# ZynqCoreBoard2.net
KiCad netlist of a schematic drawn in Altium Designer
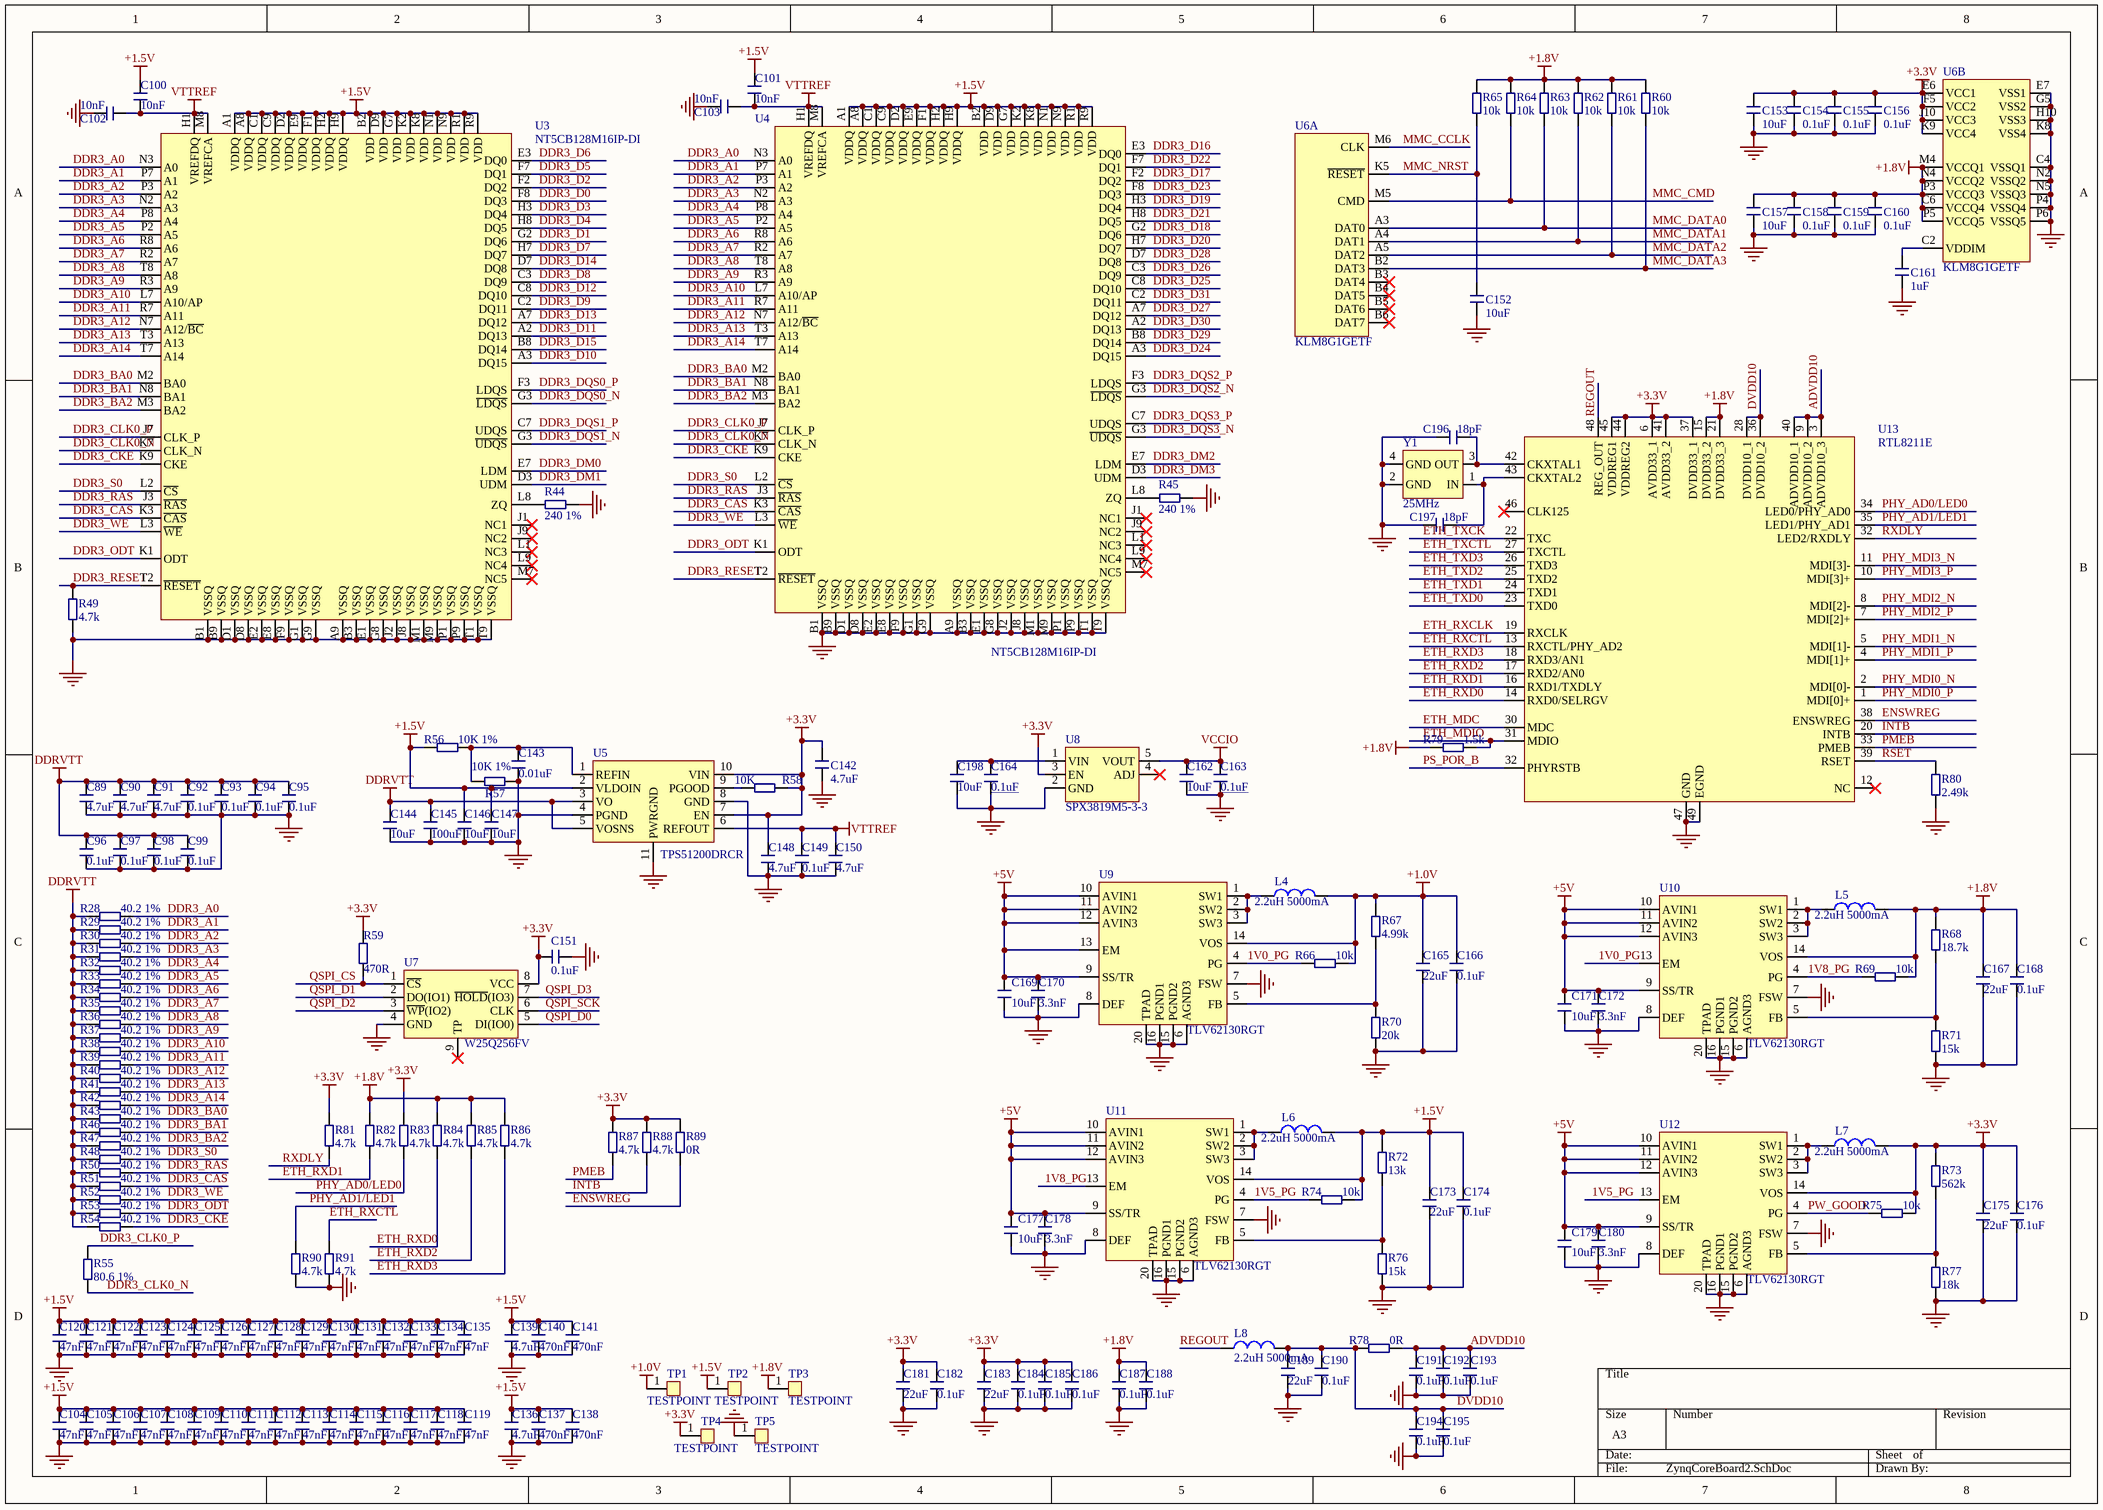
[diagram p0: ZynqCoreBoard2.SchDoc]

(export (version "E")
  (design (tool "Eeschema 10.0.6"))
  (components
    (comp (ref "C89")
      (value "4.7uF")
      (footprint "C0402")
      (libsource (lib "zynqCoreboard_SCHLIB") (part "C0402"))
    )
    (comp (ref "C90")
      (value "4.7uF")
      (footprint "C0402")
      (libsource (lib "zynqCoreboard_SCHLIB") (part "C0402"))
    )
    (comp (ref "C91")
      (value "4.7uF")
      (footprint "C0402")
      (libsource (lib "zynqCoreboard_SCHLIB") (part "C0402"))
    )
    (comp (ref "C92")
      (value "0.1uF")
      (footprint "C0402")
      (libsource (lib "zynqCoreboard_SCHLIB") (part "C0402"))
    )
    (comp (ref "C93")
      (value "0.1uF")
      (footprint "C0402")
      (libsource (lib "zynqCoreboard_SCHLIB") (part "C0402"))
    )
    (comp (ref "C94")
      (value "0.1uF")
      (footprint "C0402")
      (libsource (lib "zynqCoreboard_SCHLIB") (part "C0402"))
    )
    (comp (ref "C95")
      (value "0.1uF")
      (footprint "C0402")
      (libsource (lib "zynqCoreboard_SCHLIB") (part "C0402"))
    )
    (comp (ref "C96")
      (value "0.1uF")
      (footprint "C0402")
      (libsource (lib "zynqCoreboard_SCHLIB") (part "C0402"))
    )
    (comp (ref "C97")
      (value "0.1uF")
      (footprint "C0402")
      (libsource (lib "zynqCoreboard_SCHLIB") (part "C0402"))
    )
    (comp (ref "C98")
      (value "0.1uF")
      (footprint "C0402")
      (libsource (lib "zynqCoreboard_SCHLIB") (part "C0402"))
    )
    (comp (ref "C99")
      (value "0.1uF")
      (footprint "C0402")
      (libsource (lib "zynqCoreboard_SCHLIB") (part "C0402"))
    )
    (comp (ref "C100")
      (value "10nF")
      (footprint "C0402")
      (libsource (lib "zynqCoreboard_SCHLIB") (part "C0402"))
    )
    (comp (ref "C101")
      (value "10nF")
      (footprint "C0402")
      (libsource (lib "zynqCoreboard_SCHLIB") (part "C0402"))
    )
    (comp (ref "C102")
      (value "10nF")
      (footprint "C0402")
      (libsource (lib "zynqCoreboard_SCHLIB") (part "C0402"))
    )
    (comp (ref "C103")
      (value "10nF")
      (footprint "C0402")
      (libsource (lib "zynqCoreboard_SCHLIB") (part "C0402"))
    )
    (comp (ref "C104")
      (value "47nF")
      (footprint "C0402")
      (libsource (lib "zynqCoreboard_SCHLIB") (part "C0402"))
    )
    (comp (ref "C105")
      (value "47nF")
      (footprint "C0402")
      (libsource (lib "zynqCoreboard_SCHLIB") (part "C0402"))
    )
    (comp (ref "C106")
      (value "47nF")
      (footprint "C0402")
      (libsource (lib "zynqCoreboard_SCHLIB") (part "C0402"))
    )
    (comp (ref "C107")
      (value "47nF")
      (footprint "C0402")
      (libsource (lib "zynqCoreboard_SCHLIB") (part "C0402"))
    )
    (comp (ref "C108")
      (value "47nF")
      (footprint "C0402")
      (libsource (lib "zynqCoreboard_SCHLIB") (part "C0402"))
    )
    (comp (ref "C109")
      (value "47nF")
      (footprint "C0402")
      (libsource (lib "zynqCoreboard_SCHLIB") (part "C0402"))
    )
    (comp (ref "C110")
      (value "47nF")
      (footprint "C0402")
      (libsource (lib "zynqCoreboard_SCHLIB") (part "C0402"))
    )
    (comp (ref "C111")
      (value "47nF")
      (footprint "C0402")
      (libsource (lib "zynqCoreboard_SCHLIB") (part "C0402"))
    )
    (comp (ref "C112")
      (value "47nF")
      (footprint "C0402")
      (libsource (lib "zynqCoreboard_SCHLIB") (part "C0402"))
    )
    (comp (ref "C113")
      (value "47nF")
      (footprint "C0402")
      (libsource (lib "zynqCoreboard_SCHLIB") (part "C0402"))
    )
    (comp (ref "C114")
      (value "47nF")
      (footprint "C0402")
      (libsource (lib "zynqCoreboard_SCHLIB") (part "C0402"))
    )
    (comp (ref "C115")
      (value "47nF")
      (footprint "C0402")
      (libsource (lib "zynqCoreboard_SCHLIB") (part "C0402"))
    )
    (comp (ref "C116")
      (value "47nF")
      (footprint "C0402")
      (libsource (lib "zynqCoreboard_SCHLIB") (part "C0402"))
    )
    (comp (ref "C117")
      (value "47nF")
      (footprint "C0402")
      (libsource (lib "zynqCoreboard_SCHLIB") (part "C0402"))
    )
    (comp (ref "C118")
      (value "47nF")
      (footprint "C0402")
      (libsource (lib "zynqCoreboard_SCHLIB") (part "C0402"))
    )
    (comp (ref "C119")
      (value "47nF")
      (footprint "C0402")
      (libsource (lib "zynqCoreboard_SCHLIB") (part "C0402"))
    )
    (comp (ref "C120")
      (value "47nF")
      (footprint "C0402")
      (libsource (lib "zynqCoreboard_SCHLIB") (part "C0402"))
    )
    (comp (ref "C121")
      (value "47nF")
      (footprint "C0402")
      (libsource (lib "zynqCoreboard_SCHLIB") (part "C0402"))
    )
    (comp (ref "C122")
      (value "47nF")
      (footprint "C0402")
      (libsource (lib "zynqCoreboard_SCHLIB") (part "C0402"))
    )
    (comp (ref "C123")
      (value "47nF")
      (footprint "C0402")
      (libsource (lib "zynqCoreboard_SCHLIB") (part "C0402"))
    )
    (comp (ref "C124")
      (value "47nF")
      (footprint "C0402")
      (libsource (lib "zynqCoreboard_SCHLIB") (part "C0402"))
    )
    (comp (ref "C125")
      (value "47nF")
      (footprint "C0402")
      (libsource (lib "zynqCoreboard_SCHLIB") (part "C0402"))
    )
    (comp (ref "C126")
      (value "47nF")
      (footprint "C0402")
      (libsource (lib "zynqCoreboard_SCHLIB") (part "C0402"))
    )
    (comp (ref "C127")
      (value "47nF")
      (footprint "C0402")
      (libsource (lib "zynqCoreboard_SCHLIB") (part "C0402"))
    )
    (comp (ref "C128")
      (value "47nF")
      (footprint "C0402")
      (libsource (lib "zynqCoreboard_SCHLIB") (part "C0402"))
    )
    (comp (ref "C129")
      (value "47nF")
      (footprint "C0402")
      (libsource (lib "zynqCoreboard_SCHLIB") (part "C0402"))
    )
    (comp (ref "C130")
      (value "47nF")
      (footprint "C0402")
      (libsource (lib "zynqCoreboard_SCHLIB") (part "C0402"))
    )
    (comp (ref "C131")
      (value "47nF")
      (footprint "C0402")
      (libsource (lib "zynqCoreboard_SCHLIB") (part "C0402"))
    )
    (comp (ref "C132")
      (value "47nF")
      (footprint "C0402")
      (libsource (lib "zynqCoreboard_SCHLIB") (part "C0402"))
    )
    (comp (ref "C133")
      (value "47nF")
      (footprint "C0402")
      (libsource (lib "zynqCoreboard_SCHLIB") (part "C0402"))
    )
    (comp (ref "C134")
      (value "47nF")
      (footprint "C0402")
      (libsource (lib "zynqCoreboard_SCHLIB") (part "C0402"))
    )
    (comp (ref "C135")
      (value "47nF")
      (footprint "C0402")
      (libsource (lib "zynqCoreboard_SCHLIB") (part "C0402"))
    )
    (comp (ref "C136")
      (value "4.7uF")
      (footprint "C0402")
      (libsource (lib "zynqCoreboard_SCHLIB") (part "C0402"))
    )
    (comp (ref "C137")
      (value "470nF")
      (footprint "C0402")
      (libsource (lib "zynqCoreboard_SCHLIB") (part "C0402"))
    )
    (comp (ref "C138")
      (value "470nF")
      (footprint "C0402")
      (libsource (lib "zynqCoreboard_SCHLIB") (part "C0402"))
    )
    (comp (ref "C139")
      (value "4.7uF")
      (footprint "C0402")
      (libsource (lib "zynqCoreboard_SCHLIB") (part "C0402"))
    )
    (comp (ref "C140")
      (value "470nF")
      (footprint "C0402")
      (libsource (lib "zynqCoreboard_SCHLIB") (part "C0402"))
    )
    (comp (ref "C141")
      (value "470nF")
      (footprint "C0402")
      (libsource (lib "zynqCoreboard_SCHLIB") (part "C0402"))
    )
    (comp (ref "C142")
      (value "4.7uF")
      (footprint "C0402")
      (libsource (lib "zynqCoreboard_SCHLIB") (part "C0402"))
    )
    (comp (ref "C143")
      (value "0.01uF")
      (footprint "C0402")
      (libsource (lib "zynqCoreboard_SCHLIB") (part "C0402"))
    )
    (comp (ref "C144")
      (value "10uF")
      (footprint "C0603")
      (libsource (lib "zynqCoreboard_SCHLIB") (part "C0603"))
    )
    (comp (ref "C145")
      (value "100uF")
      (footprint "C1206")
      (libsource (lib "zynqCoreboard_SCHLIB") (part "C1206"))
    )
    (comp (ref "C146")
      (value "10uF")
      (footprint "C0603")
      (libsource (lib "zynqCoreboard_SCHLIB") (part "C0603"))
    )
    (comp (ref "C147")
      (value "10uF")
      (footprint "C0603")
      (libsource (lib "zynqCoreboard_SCHLIB") (part "C0603"))
    )
    (comp (ref "C148")
      (value "4.7uF")
      (footprint "C0402")
      (libsource (lib "zynqCoreboard_SCHLIB") (part "C0402"))
    )
    (comp (ref "C149")
      (value "0.1uF")
      (footprint "C0402")
      (libsource (lib "zynqCoreboard_SCHLIB") (part "C0402"))
    )
    (comp (ref "C150")
      (value "4.7uF")
      (footprint "C0402")
      (libsource (lib "zynqCoreboard_SCHLIB") (part "C0402"))
    )
    (comp (ref "C151")
      (value "0.1uF")
      (footprint "C0402")
      (libsource (lib "zynqCoreboard_SCHLIB") (part "C0402"))
    )
    (comp (ref "C152")
      (value "10uF")
      (footprint "C0603")
      (libsource (lib "zynqCoreboard_SCHLIB") (part "C0603"))
    )
    (comp (ref "C153")
      (value "10uF")
      (footprint "C0603")
      (libsource (lib "zynqCoreboard_SCHLIB") (part "C0603"))
    )
    (comp (ref "C154")
      (value "0.1uF")
      (footprint "C0402")
      (libsource (lib "zynqCoreboard_SCHLIB") (part "C0402"))
    )
    (comp (ref "C155")
      (value "0.1uF")
      (footprint "C0402")
      (libsource (lib "zynqCoreboard_SCHLIB") (part "C0402"))
    )
    (comp (ref "C156")
      (value "0.1uF")
      (footprint "C0402")
      (libsource (lib "zynqCoreboard_SCHLIB") (part "C0402"))
    )
    (comp (ref "C157")
      (value "10uF")
      (footprint "C0603")
      (libsource (lib "zynqCoreboard_SCHLIB") (part "C0603"))
    )
    (comp (ref "C158")
      (value "0.1uF")
      (footprint "C0402")
      (libsource (lib "zynqCoreboard_SCHLIB") (part "C0402"))
    )
    (comp (ref "C159")
      (value "0.1uF")
      (footprint "C0402")
      (libsource (lib "zynqCoreboard_SCHLIB") (part "C0402"))
    )
    (comp (ref "C160")
      (value "0.1uF")
      (footprint "C0402")
      (libsource (lib "zynqCoreboard_SCHLIB") (part "C0402"))
    )
    (comp (ref "C161")
      (value "1uF")
      (footprint "C0402")
      (libsource (lib "zynqCoreboard_SCHLIB") (part "C0402"))
    )
    (comp (ref "C162")
      (value "10uF")
      (footprint "C0805")
      (libsource (lib "zynqCoreboard_SCHLIB") (part "C0805"))
    )
    (comp (ref "C163")
      (value "0.1uF")
      (footprint "C0402")
      (libsource (lib "zynqCoreboard_SCHLIB") (part "C0402"))
    )
    (comp (ref "C164")
      (value "0.1uF")
      (footprint "C0402")
      (libsource (lib "zynqCoreboard_SCHLIB") (part "C0402"))
    )
    (comp (ref "C165")
      (value "22uF")
      (footprint "C0805")
      (libsource (lib "zynqCoreboard_SCHLIB") (part "C0805"))
    )
    (comp (ref "C166")
      (value "0.1uF")
      (footprint "C0402")
      (libsource (lib "zynqCoreboard_SCHLIB") (part "C0402"))
    )
    (comp (ref "C167")
      (value "22uF")
      (footprint "C0805")
      (libsource (lib "zynqCoreboard_SCHLIB") (part "C0805"))
    )
    (comp (ref "C168")
      (value "0.1uF")
      (footprint "C0402")
      (libsource (lib "zynqCoreboard_SCHLIB") (part "C0402"))
    )
    (comp (ref "C169")
      (value "10uF")
      (footprint "C0603")
      (libsource (lib "zynqCoreboard_SCHLIB") (part "C0603"))
    )
    (comp (ref "C170")
      (value "3.3nF")
      (footprint "C0402")
      (libsource (lib "zynqCoreboard_SCHLIB") (part "C0402"))
    )
    (comp (ref "C171")
      (value "10uF")
      (footprint "C0603")
      (libsource (lib "zynqCoreboard_SCHLIB") (part "C0603"))
    )
    (comp (ref "C172")
      (value "3.3nF")
      (footprint "C0402")
      (libsource (lib "zynqCoreboard_SCHLIB") (part "C0402"))
    )
    (comp (ref "C173")
      (value "22uF")
      (footprint "C0805")
      (libsource (lib "zynqCoreboard_SCHLIB") (part "C0805"))
    )
    (comp (ref "C174")
      (value "0.1uF")
      (footprint "C0402")
      (libsource (lib "zynqCoreboard_SCHLIB") (part "C0402"))
    )
    (comp (ref "C175")
      (value "22uF")
      (footprint "C0805")
      (libsource (lib "zynqCoreboard_SCHLIB") (part "C0805"))
    )
    (comp (ref "C176")
      (value "0.1uF")
      (footprint "C0402")
      (libsource (lib "zynqCoreboard_SCHLIB") (part "C0402"))
    )
    (comp (ref "C177")
      (value "10uF")
      (footprint "C0603")
      (libsource (lib "zynqCoreboard_SCHLIB") (part "C0603"))
    )
    (comp (ref "C178")
      (value "3.3nF")
      (footprint "C0402")
      (libsource (lib "zynqCoreboard_SCHLIB") (part "C0402"))
    )
    (comp (ref "C179")
      (value "10uF")
      (footprint "C0603")
      (libsource (lib "zynqCoreboard_SCHLIB") (part "C0603"))
    )
    (comp (ref "C180")
      (value "3.3nF")
      (footprint "C0402")
      (libsource (lib "zynqCoreboard_SCHLIB") (part "C0402"))
    )
    (comp (ref "C181")
      (value "22uF")
      (footprint "C0805")
      (libsource (lib "zynqCoreboard_SCHLIB") (part "C0805"))
    )
    (comp (ref "C182")
      (value "0.1uF")
      (footprint "C0402")
      (libsource (lib "zynqCoreboard_SCHLIB") (part "C0402"))
    )
    (comp (ref "C183")
      (value "22uF")
      (footprint "C0805")
      (libsource (lib "zynqCoreboard_SCHLIB") (part "C0805"))
    )
    (comp (ref "C184")
      (value "0.1uF")
      (footprint "C0402")
      (libsource (lib "zynqCoreboard_SCHLIB") (part "C0402"))
    )
    (comp (ref "C185")
      (value "0.1uF")
      (footprint "C0402")
      (libsource (lib "zynqCoreboard_SCHLIB") (part "C0402"))
    )
    (comp (ref "C186")
      (value "0.1uF")
      (footprint "C0402")
      (libsource (lib "zynqCoreboard_SCHLIB") (part "C0402"))
    )
    (comp (ref "C187")
      (value "0.1uF")
      (footprint "C0402")
      (libsource (lib "zynqCoreboard_SCHLIB") (part "C0402"))
    )
    (comp (ref "C188")
      (value "0.1uF")
      (footprint "C0402")
      (libsource (lib "zynqCoreboard_SCHLIB") (part "C0402"))
    )
    (comp (ref "C189")
      (value "22uF")
      (footprint "C0603")
      (libsource (lib "zynqCoreboard_SCHLIB") (part "C0603"))
    )
    (comp (ref "C190")
      (value "0.1uF")
      (footprint "C0402")
      (libsource (lib "zynqCoreboard_SCHLIB") (part "C0402"))
    )
    (comp (ref "C191")
      (value "0.1uF")
      (footprint "C0402")
      (libsource (lib "zynqCoreboard_SCHLIB") (part "C0402"))
    )
    (comp (ref "C192")
      (value "0.1uF")
      (footprint "C0402")
      (libsource (lib "zynqCoreboard_SCHLIB") (part "C0402"))
    )
    (comp (ref "C193")
      (value "0.1uF")
      (footprint "C0402")
      (libsource (lib "zynqCoreboard_SCHLIB") (part "C0402"))
    )
    (comp (ref "C194")
      (value "0.1uF")
      (footprint "C0402")
      (libsource (lib "zynqCoreboard_SCHLIB") (part "C0402"))
    )
    (comp (ref "C195")
      (value "0.1uF")
      (footprint "C0402")
      (libsource (lib "zynqCoreboard_SCHLIB") (part "C0402"))
    )
    (comp (ref "C196")
      (value "18pF")
      (footprint "C0402")
      (libsource (lib "zynqCoreboard_SCHLIB") (part "C0402"))
    )
    (comp (ref "C197")
      (value "18pF")
      (footprint "C0402")
      (libsource (lib "zynqCoreboard_SCHLIB") (part "C0402"))
    )
    (comp (ref "C198")
      (value "10uF")
      (footprint "C0805")
      (libsource (lib "zynqCoreboard_SCHLIB") (part "C0805"))
    )
    (comp (ref "L4")
      (value "2.2uH 5000mA")
      (footprint "L-SMD-0630")
      (libsource (lib "zynqCoreboard_SCHLIB") (part "L_2.2uH_5000mA"))
    )
    (comp (ref "L5")
      (value "2.2uH 5000mA")
      (footprint "L-SMD-0630")
      (libsource (lib "zynqCoreboard_SCHLIB") (part "L_2.2uH_5000mA"))
    )
    (comp (ref "L6")
      (value "2.2uH 5000mA")
      (footprint "L-SMD-0630")
      (libsource (lib "zynqCoreboard_SCHLIB") (part "L_2.2uH_5000mA"))
    )
    (comp (ref "L7")
      (value "2.2uH 5000mA")
      (footprint "L-SMD-0630")
      (libsource (lib "zynqCoreboard_SCHLIB") (part "L_2.2uH_5000mA"))
    )
    (comp (ref "L8")
      (value "2.2uH 5000mA")
      (footprint "L0603")
      (libsource (lib "zynqCoreboard_SCHLIB") (part "L0603"))
    )
    (comp (ref "R28")
      (value "40.2 1%")
      (footprint "R0402")
      (libsource (lib "zynqCoreboard_SCHLIB") (part "R0402"))
    )
    (comp (ref "R29")
      (value "40.2 1%")
      (footprint "R0402")
      (libsource (lib "zynqCoreboard_SCHLIB") (part "R0402"))
    )
    (comp (ref "R30")
      (value "40.2 1%")
      (footprint "R0402")
      (libsource (lib "zynqCoreboard_SCHLIB") (part "R0402"))
    )
    (comp (ref "R31")
      (value "40.2 1%")
      (footprint "R0402")
      (libsource (lib "zynqCoreboard_SCHLIB") (part "R0402"))
    )
    (comp (ref "R32")
      (value "40.2 1%")
      (footprint "R0402")
      (libsource (lib "zynqCoreboard_SCHLIB") (part "R0402"))
    )
    (comp (ref "R33")
      (value "40.2 1%")
      (footprint "R0402")
      (libsource (lib "zynqCoreboard_SCHLIB") (part "R0402"))
    )
    (comp (ref "R34")
      (value "40.2 1%")
      (footprint "R0402")
      (libsource (lib "zynqCoreboard_SCHLIB") (part "R0402"))
    )
    (comp (ref "R35")
      (value "40.2 1%")
      (footprint "R0402")
      (libsource (lib "zynqCoreboard_SCHLIB") (part "R0402"))
    )
    (comp (ref "R36")
      (value "40.2 1%")
      (footprint "R0402")
      (libsource (lib "zynqCoreboard_SCHLIB") (part "R0402"))
    )
    (comp (ref "R37")
      (value "40.2 1%")
      (footprint "R0402")
      (libsource (lib "zynqCoreboard_SCHLIB") (part "R0402"))
    )
    (comp (ref "R38")
      (value "40.2 1%")
      (footprint "R0402")
      (libsource (lib "zynqCoreboard_SCHLIB") (part "R0402"))
    )
    (comp (ref "R39")
      (value "40.2 1%")
      (footprint "R0402")
      (libsource (lib "zynqCoreboard_SCHLIB") (part "R0402"))
    )
    (comp (ref "R40")
      (value "40.2 1%")
      (footprint "R0402")
      (libsource (lib "zynqCoreboard_SCHLIB") (part "R0402"))
    )
    (comp (ref "R41")
      (value "40.2 1%")
      (footprint "R0402")
      (libsource (lib "zynqCoreboard_SCHLIB") (part "R0402"))
    )
    (comp (ref "R42")
      (value "40.2 1%")
      (footprint "R0402")
      (libsource (lib "zynqCoreboard_SCHLIB") (part "R0402"))
    )
    (comp (ref "R43")
      (value "40.2 1%")
      (footprint "R0402")
      (libsource (lib "zynqCoreboard_SCHLIB") (part "R0402"))
    )
    (comp (ref "R44")
      (value "240 1%")
      (footprint "R0402")
      (libsource (lib "zynqCoreboard_SCHLIB") (part "R0402"))
    )
    (comp (ref "R45")
      (value "240 1%")
      (footprint "R0402")
      (libsource (lib "zynqCoreboard_SCHLIB") (part "R0402"))
    )
    (comp (ref "R46")
      (value "40.2 1%")
      (footprint "R0402")
      (libsource (lib "zynqCoreboard_SCHLIB") (part "R0402"))
    )
    (comp (ref "R47")
      (value "40.2 1%")
      (footprint "R0402")
      (libsource (lib "zynqCoreboard_SCHLIB") (part "R0402"))
    )
    (comp (ref "R48")
      (value "40.2 1%")
      (footprint "R0402")
      (libsource (lib "zynqCoreboard_SCHLIB") (part "R0402"))
    )
    (comp (ref "R49")
      (value "4.7k")
      (footprint "R0402")
      (libsource (lib "zynqCoreboard_SCHLIB") (part "R0402"))
    )
    (comp (ref "R50")
      (value "40.2 1%")
      (footprint "R0402")
      (libsource (lib "zynqCoreboard_SCHLIB") (part "R0402"))
    )
    (comp (ref "R51")
      (value "40.2 1%")
      (footprint "R0402")
      (libsource (lib "zynqCoreboard_SCHLIB") (part "R0402"))
    )
    (comp (ref "R52")
      (value "40.2 1%")
      (footprint "R0402")
      (libsource (lib "zynqCoreboard_SCHLIB") (part "R0402"))
    )
    (comp (ref "R53")
      (value "40.2 1%")
      (footprint "R0402")
      (libsource (lib "zynqCoreboard_SCHLIB") (part "R0402"))
    )
    (comp (ref "R54")
      (value "40.2 1%")
      (footprint "R0402")
      (libsource (lib "zynqCoreboard_SCHLIB") (part "R0402"))
    )
    (comp (ref "R55")
      (value "80.6 1%")
      (footprint "R0402")
      (libsource (lib "zynqCoreboard_SCHLIB") (part "R0402"))
    )
    (comp (ref "R56")
      (value "10K 1%")
      (footprint "R0402")
      (libsource (lib "zynqCoreboard_SCHLIB") (part "R0402"))
    )
    (comp (ref "R57")
      (value "10K 1%")
      (footprint "R0402")
      (libsource (lib "zynqCoreboard_SCHLIB") (part "R0402"))
    )
    (comp (ref "R58")
      (value "10K")
      (footprint "R0402")
      (libsource (lib "zynqCoreboard_SCHLIB") (part "R0402"))
    )
    (comp (ref "R59")
      (value "470R")
      (footprint "R0402")
      (libsource (lib "zynqCoreboard_SCHLIB") (part "R0402"))
    )
    (comp (ref "R60")
      (value "10k")
      (footprint "R0402")
      (libsource (lib "zynqCoreboard_SCHLIB") (part "R0402"))
    )
    (comp (ref "R61")
      (value "10k")
      (footprint "R0402")
      (libsource (lib "zynqCoreboard_SCHLIB") (part "R0402"))
    )
    (comp (ref "R62")
      (value "10k")
      (footprint "R0402")
      (libsource (lib "zynqCoreboard_SCHLIB") (part "R0402"))
    )
    (comp (ref "R63")
      (value "10k")
      (footprint "R0402")
      (libsource (lib "zynqCoreboard_SCHLIB") (part "R0402"))
    )
    (comp (ref "R64")
      (value "10k")
      (footprint "R0402")
      (libsource (lib "zynqCoreboard_SCHLIB") (part "R0402"))
    )
    (comp (ref "R65")
      (value "10k")
      (footprint "R0402")
      (libsource (lib "zynqCoreboard_SCHLIB") (part "R0402"))
    )
    (comp (ref "R66")
      (value "10k")
      (footprint "R0402")
      (libsource (lib "zynqCoreboard_SCHLIB") (part "R0402"))
    )
    (comp (ref "R67")
      (value "4.99k")
      (footprint "R0402")
      (libsource (lib "zynqCoreboard_SCHLIB") (part "R0402"))
    )
    (comp (ref "R68")
      (value "18.7k")
      (footprint "R0402")
      (libsource (lib "zynqCoreboard_SCHLIB") (part "R0402"))
    )
    (comp (ref "R69")
      (value "10k")
      (footprint "R0402")
      (libsource (lib "zynqCoreboard_SCHLIB") (part "R0402"))
    )
    (comp (ref "R70")
      (value "20k")
      (footprint "R0402")
      (libsource (lib "zynqCoreboard_SCHLIB") (part "R0402"))
    )
    (comp (ref "R71")
      (value "15k")
      (footprint "R0402")
      (libsource (lib "zynqCoreboard_SCHLIB") (part "R0402"))
    )
    (comp (ref "R72")
      (value "13k")
      (footprint "R0402")
      (libsource (lib "zynqCoreboard_SCHLIB") (part "R0402"))
    )
    (comp (ref "R73")
      (value "562k")
      (footprint "R0402")
      (libsource (lib "zynqCoreboard_SCHLIB") (part "R0402"))
    )
    (comp (ref "R74")
      (value "10k")
      (footprint "R0402")
      (libsource (lib "zynqCoreboard_SCHLIB") (part "R0402"))
    )
    (comp (ref "R75")
      (value "10k")
      (footprint "R0402")
      (libsource (lib "zynqCoreboard_SCHLIB") (part "R0402"))
    )
    (comp (ref "R76")
      (value "15k")
      (footprint "R0402")
      (libsource (lib "zynqCoreboard_SCHLIB") (part "R0402"))
    )
    (comp (ref "R77")
      (value "18k")
      (footprint "R0402")
      (libsource (lib "zynqCoreboard_SCHLIB") (part "R0402"))
    )
    (comp (ref "R78")
      (value "0R")
      (footprint "R0402")
      (libsource (lib "zynqCoreboard_SCHLIB") (part "R0402"))
    )
    (comp (ref "R79")
      (value "1.5k")
      (footprint "R0402")
      (libsource (lib "zynqCoreboard_SCHLIB") (part "R0402"))
    )
    (comp (ref "R80")
      (value "2.49k")
      (footprint "R0402")
      (libsource (lib "zynqCoreboard_SCHLIB") (part "R0402"))
    )
    (comp (ref "R81")
      (value "4.7k")
      (footprint "R0402")
      (libsource (lib "zynqCoreboard_SCHLIB") (part "R0402"))
    )
    (comp (ref "R82")
      (value "4.7k")
      (footprint "R0402")
      (libsource (lib "zynqCoreboard_SCHLIB") (part "R0402"))
    )
    (comp (ref "R83")
      (value "4.7k")
      (footprint "R0402")
      (libsource (lib "zynqCoreboard_SCHLIB") (part "R0402"))
    )
    (comp (ref "R84")
      (value "4.7k")
      (footprint "R0402")
      (libsource (lib "zynqCoreboard_SCHLIB") (part "R0402"))
    )
    (comp (ref "R85")
      (value "4.7k")
      (footprint "R0402")
      (libsource (lib "zynqCoreboard_SCHLIB") (part "R0402"))
    )
    (comp (ref "R86")
      (value "4.7k")
      (footprint "R0402")
      (libsource (lib "zynqCoreboard_SCHLIB") (part "R0402"))
    )
    (comp (ref "R87")
      (value "4.7k")
      (footprint "R0402")
      (libsource (lib "zynqCoreboard_SCHLIB") (part "R0402"))
    )
    (comp (ref "R88")
      (value "4.7k")
      (footprint "R0402")
      (libsource (lib "zynqCoreboard_SCHLIB") (part "R0402"))
    )
    (comp (ref "R89")
      (value "0R")
      (footprint "R0402")
      (libsource (lib "zynqCoreboard_SCHLIB") (part "R0402"))
    )
    (comp (ref "R90")
      (value "4.7k")
      (footprint "R0402")
      (libsource (lib "zynqCoreboard_SCHLIB") (part "R0402"))
    )
    (comp (ref "R91")
      (value "4.7k")
      (footprint "R0402")
      (libsource (lib "zynqCoreboard_SCHLIB") (part "R0402"))
    )
    (comp (ref "TP1")
      (value "TESTPOINT")
      (footprint "FPAD_1")
      (libsource (lib "zynqCoreboard_SCHLIB") (part "TESTPOINT"))
    )
    (comp (ref "TP2")
      (value "TESTPOINT")
      (footprint "FPAD_1")
      (libsource (lib "zynqCoreboard_SCHLIB") (part "TESTPOINT"))
    )
    (comp (ref "TP3")
      (value "TESTPOINT")
      (footprint "FPAD_1")
      (libsource (lib "zynqCoreboard_SCHLIB") (part "TESTPOINT"))
    )
    (comp (ref "TP4")
      (value "TESTPOINT")
      (footprint "FPAD_1")
      (libsource (lib "zynqCoreboard_SCHLIB") (part "TESTPOINT"))
    )
    (comp (ref "TP5")
      (value "TESTPOINT")
      (footprint "FPAD_1")
      (libsource (lib "zynqCoreboard_SCHLIB") (part "TESTPOINT"))
    )
    (comp (ref "U3")
      (value "NT5CB128M16IP-DI")
      (footprint "FBGA_96")
      (libsource (lib "zynqCoreboard_SCHLIB") (part "NT5CB128M16IP-DI"))
    )
    (comp (ref "U4")
      (value "NT5CB128M16IP-DI")
      (footprint "FBGA_96")
      (libsource (lib "zynqCoreboard_SCHLIB") (part "NT5CB128M16IP-DI"))
    )
    (comp (ref "U5")
      (value "TPS51200DRCR")
      (footprint "TPS_QFN10")
      (libsource (lib "zynqCoreboard_SCHLIB") (part "TPS51200DRCR"))
    )
    (comp (ref "U6")
      (value "KLM8G1GETF")
      (footprint "VFBGA")
      (libsource (lib "zynqCoreboard_SCHLIB") (part "KLM8G1GETF"))
    )
    (comp (ref "U7")
      (value "W25Q256FV")
      (footprint "W25Q256FV")
      (libsource (lib "zynqCoreboard_SCHLIB") (part "W25Q256FV"))
    )
    (comp (ref "U8")
      (value "SPX3819M5-3-3")
      (footprint "SOT23-5")
      (libsource (lib "zynqCoreboard_SCHLIB") (part "SPX3819M5-3-3"))
    )
    (comp (ref "U9")
      (value "TLV62130RGT")
      (footprint "QFN16_3x3")
      (libsource (lib "zynqCoreboard_SCHLIB") (part "TLV62130RGT"))
    )
    (comp (ref "U10")
      (value "TLV62130RGT")
      (footprint "QFN16_3x3")
      (libsource (lib "zynqCoreboard_SCHLIB") (part "TLV62130RGT"))
    )
    (comp (ref "U11")
      (value "TLV62130RGT")
      (footprint "QFN16_3x3")
      (libsource (lib "zynqCoreboard_SCHLIB") (part "TLV62130RGT"))
    )
    (comp (ref "U12")
      (value "TLV62130RGT")
      (footprint "QFN16_3x3")
      (libsource (lib "zynqCoreboard_SCHLIB") (part "TLV62130RGT"))
    )
    (comp (ref "U13")
      (value "RTL8211E")
      (footprint "QFN48")
      (libsource (lib "zynqCoreboard_SCHLIB") (part "RTL8211E"))
    )
    (comp (ref "Y1")
      (value "25MHz")
      (footprint "OSC 3225-4P")
      (libsource (lib "zynqCoreboard_SCHLIB") (part "XTAL_25MHz_3225"))
    )
  )
  (nets
    (net (code "1") (name "+1.0V") (class "Default")
      (node (ref "C165") (pin "2") (pinfunction "2_2") (pintype "passive"))
      (node (ref "C166") (pin "2") (pinfunction "2_2") (pintype "passive"))
      (node (ref "L4") (pin "2") (pinfunction "2_2") (pintype "passive"))
      (node (ref "R66") (pin "2") (pinfunction "2_2") (pintype "passive"))
      (node (ref "R67") (pin "2") (pinfunction "2_2") (pintype "passive"))
      (node (ref "TP1") (pin "1") (pinfunction "1_1") (pintype "passive"))
      (node (ref "U9") (pin "14") (pinfunction "VOS_14") (pintype "passive"))
    )
    (net (code "2") (name "+1.5V") (class "Default")
      (node (ref "C100") (pin "2") (pinfunction "2_2") (pintype "passive"))
      (node (ref "C101") (pin "2") (pinfunction "2_2") (pintype "passive"))
      (node (ref "C104") (pin "2") (pinfunction "2_2") (pintype "passive"))
      (node (ref "C105") (pin "2") (pinfunction "2_2") (pintype "passive"))
      (node (ref "C106") (pin "2") (pinfunction "2_2") (pintype "passive"))
      (node (ref "C107") (pin "2") (pinfunction "2_2") (pintype "passive"))
      (node (ref "C108") (pin "2") (pinfunction "2_2") (pintype "passive"))
      (node (ref "C109") (pin "2") (pinfunction "2_2") (pintype "passive"))
      (node (ref "C110") (pin "2") (pinfunction "2_2") (pintype "passive"))
      (node (ref "C111") (pin "2") (pinfunction "2_2") (pintype "passive"))
      (node (ref "C112") (pin "2") (pinfunction "2_2") (pintype "passive"))
      (node (ref "C113") (pin "2") (pinfunction "2_2") (pintype "passive"))
      (node (ref "C114") (pin "2") (pinfunction "2_2") (pintype "passive"))
      (node (ref "C115") (pin "2") (pinfunction "2_2") (pintype "passive"))
      (node (ref "C116") (pin "2") (pinfunction "2_2") (pintype "passive"))
      (node (ref "C117") (pin "2") (pinfunction "2_2") (pintype "passive"))
      (node (ref "C118") (pin "2") (pinfunction "2_2") (pintype "passive"))
      (node (ref "C119") (pin "2") (pinfunction "2_2") (pintype "passive"))
      (node (ref "C120") (pin "2") (pinfunction "2_2") (pintype "passive"))
      (node (ref "C121") (pin "2") (pinfunction "2_2") (pintype "passive"))
      (node (ref "C122") (pin "2") (pinfunction "2_2") (pintype "passive"))
      (node (ref "C123") (pin "2") (pinfunction "2_2") (pintype "passive"))
      (node (ref "C124") (pin "2") (pinfunction "2_2") (pintype "passive"))
      (node (ref "C125") (pin "2") (pinfunction "2_2") (pintype "passive"))
      (node (ref "C126") (pin "2") (pinfunction "2_2") (pintype "passive"))
      (node (ref "C127") (pin "2") (pinfunction "2_2") (pintype "passive"))
      (node (ref "C128") (pin "2") (pinfunction "2_2") (pintype "passive"))
      (node (ref "C129") (pin "2") (pinfunction "2_2") (pintype "passive"))
      (node (ref "C130") (pin "2") (pinfunction "2_2") (pintype "passive"))
      (node (ref "C131") (pin "2") (pinfunction "2_2") (pintype "passive"))
      (node (ref "C132") (pin "2") (pinfunction "2_2") (pintype "passive"))
      (node (ref "C133") (pin "2") (pinfunction "2_2") (pintype "passive"))
      (node (ref "C134") (pin "2") (pinfunction "2_2") (pintype "passive"))
      (node (ref "C135") (pin "2") (pinfunction "2_2") (pintype "passive"))
      (node (ref "C136") (pin "2") (pinfunction "2_2") (pintype "passive"))
      (node (ref "C137") (pin "2") (pinfunction "2_2") (pintype "passive"))
      (node (ref "C138") (pin "2") (pinfunction "2_2") (pintype "passive"))
      (node (ref "C139") (pin "2") (pinfunction "2_2") (pintype "passive"))
      (node (ref "C140") (pin "2") (pinfunction "2_2") (pintype "passive"))
      (node (ref "C141") (pin "2") (pinfunction "2_2") (pintype "passive"))
      (node (ref "C146") (pin "2") (pinfunction "2_2") (pintype "passive"))
      (node (ref "C147") (pin "2") (pinfunction "2_2") (pintype "passive"))
      (node (ref "C173") (pin "2") (pinfunction "2_2") (pintype "passive"))
      (node (ref "C174") (pin "2") (pinfunction "2_2") (pintype "passive"))
      (node (ref "L6") (pin "2") (pinfunction "2_2") (pintype "passive"))
      (node (ref "R56") (pin "1") (pinfunction "1_1") (pintype "passive"))
      (node (ref "R72") (pin "2") (pinfunction "2_2") (pintype "passive"))
      (node (ref "R74") (pin "2") (pinfunction "2_2") (pintype "passive"))
      (node (ref "TP2") (pin "1") (pinfunction "1_1") (pintype "passive"))
      (node (ref "U11") (pin "14") (pinfunction "VOS_14") (pintype "passive"))
      (node (ref "U3") (pin "A1") (pinfunction "VDDQ_A1") (pintype "passive"))
      (node (ref "U3") (pin "A8") (pinfunction "VDDQ_A8") (pintype "passive"))
      (node (ref "U3") (pin "B2") (pinfunction "VDD_B2") (pintype "passive"))
      (node (ref "U3") (pin "C1") (pinfunction "VDDQ_C1") (pintype "passive"))
      (node (ref "U3") (pin "C9") (pinfunction "VDDQ_C9") (pintype "passive"))
      (node (ref "U3") (pin "D2") (pinfunction "VDDQ_D2") (pintype "passive"))
      (node (ref "U3") (pin "D9") (pinfunction "VDD_D9") (pintype "passive"))
      (node (ref "U3") (pin "E9") (pinfunction "VDDQ_E9") (pintype "passive"))
      (node (ref "U3") (pin "F1") (pinfunction "VDDQ_F1") (pintype "passive"))
      (node (ref "U3") (pin "G7") (pinfunction "VDD_G7") (pintype "passive"))
      (node (ref "U3") (pin "H2") (pinfunction "VDDQ_H2") (pintype "passive"))
      (node (ref "U3") (pin "H9") (pinfunction "VDDQ_H9") (pintype "passive"))
      (node (ref "U3") (pin "K2") (pinfunction "VDD_K2") (pintype "passive"))
      (node (ref "U3") (pin "K8") (pinfunction "VDD_K8") (pintype "passive"))
      (node (ref "U3") (pin "N1") (pinfunction "VDD_N1") (pintype "passive"))
      (node (ref "U3") (pin "N9") (pinfunction "VDD_N9") (pintype "passive"))
      (node (ref "U3") (pin "R1") (pinfunction "VDD_R1") (pintype "passive"))
      (node (ref "U3") (pin "R9") (pinfunction "VDD_R9") (pintype "passive"))
      (node (ref "U4") (pin "A1") (pinfunction "VDDQ_A1") (pintype "passive"))
      (node (ref "U4") (pin "A8") (pinfunction "VDDQ_A8") (pintype "passive"))
      (node (ref "U4") (pin "B2") (pinfunction "VDD_B2") (pintype "passive"))
      (node (ref "U4") (pin "C1") (pinfunction "VDDQ_C1") (pintype "passive"))
      (node (ref "U4") (pin "C9") (pinfunction "VDDQ_C9") (pintype "passive"))
      (node (ref "U4") (pin "D2") (pinfunction "VDDQ_D2") (pintype "passive"))
      (node (ref "U4") (pin "D9") (pinfunction "VDD_D9") (pintype "passive"))
      (node (ref "U4") (pin "E9") (pinfunction "VDDQ_E9") (pintype "passive"))
      (node (ref "U4") (pin "F1") (pinfunction "VDDQ_F1") (pintype "passive"))
      (node (ref "U4") (pin "G7") (pinfunction "VDD_G7") (pintype "passive"))
      (node (ref "U4") (pin "H2") (pinfunction "VDDQ_H2") (pintype "passive"))
      (node (ref "U4") (pin "H9") (pinfunction "VDDQ_H9") (pintype "passive"))
      (node (ref "U4") (pin "K2") (pinfunction "VDD_K2") (pintype "passive"))
      (node (ref "U4") (pin "K8") (pinfunction "VDD_K8") (pintype "passive"))
      (node (ref "U4") (pin "N1") (pinfunction "VDD_N1") (pintype "passive"))
      (node (ref "U4") (pin "N9") (pinfunction "VDD_N9") (pintype "passive"))
      (node (ref "U4") (pin "R1") (pinfunction "VDD_R1") (pintype "passive"))
      (node (ref "U4") (pin "R9") (pinfunction "VDD_R9") (pintype "passive"))
      (node (ref "U5") (pin "2") (pinfunction "VLDOIN_2") (pintype "passive"))
    )
    (net (code "3") (name "+1.8V") (class "Default")
      (node (ref "C157") (pin "2") (pinfunction "2_2") (pintype "passive"))
      (node (ref "C158") (pin "2") (pinfunction "2_2") (pintype "passive"))
      (node (ref "C159") (pin "2") (pinfunction "2_2") (pintype "passive"))
      (node (ref "C160") (pin "2") (pinfunction "2_2") (pintype "passive"))
      (node (ref "C167") (pin "2") (pinfunction "2_2") (pintype "passive"))
      (node (ref "C168") (pin "2") (pinfunction "2_2") (pintype "passive"))
      (node (ref "C187") (pin "2") (pinfunction "2_2") (pintype "passive"))
      (node (ref "C188") (pin "2") (pinfunction "2_2") (pintype "passive"))
      (node (ref "L5") (pin "2") (pinfunction "2_2") (pintype "passive"))
      (node (ref "R60") (pin "2") (pinfunction "2_2") (pintype "passive"))
      (node (ref "R61") (pin "2") (pinfunction "2_2") (pintype "passive"))
      (node (ref "R62") (pin "2") (pinfunction "2_2") (pintype "passive"))
      (node (ref "R63") (pin "2") (pinfunction "2_2") (pintype "passive"))
      (node (ref "R64") (pin "2") (pinfunction "2_2") (pintype "passive"))
      (node (ref "R65") (pin "2") (pinfunction "2_2") (pintype "passive"))
      (node (ref "R68") (pin "2") (pinfunction "2_2") (pintype "passive"))
      (node (ref "R69") (pin "2") (pinfunction "2_2") (pintype "passive"))
      (node (ref "R79") (pin "1") (pinfunction "1_1") (pintype "passive"))
      (node (ref "R82") (pin "2") (pinfunction "2_2") (pintype "passive"))
      (node (ref "R84") (pin "2") (pinfunction "2_2") (pintype "passive"))
      (node (ref "R85") (pin "2") (pinfunction "2_2") (pintype "passive"))
      (node (ref "R86") (pin "2") (pinfunction "2_2") (pintype "passive"))
      (node (ref "TP3") (pin "1") (pinfunction "1_1") (pintype "passive"))
      (node (ref "U10") (pin "14") (pinfunction "VOS_14") (pintype "passive"))
      (node (ref "U13") (pin "15") (pinfunction "DVDD33_2_15") (pintype "passive"))
      (node (ref "U13") (pin "21") (pinfunction "DVDD33_3_21") (pintype "passive"))
      (node (ref "U6") (pin "C6") (pinfunction "VCCQ4_C6") (pintype "passive"))
      (node (ref "U6") (pin "M4") (pinfunction "VCCQ1_M4") (pintype "passive"))
      (node (ref "U6") (pin "N4") (pinfunction "VCCQ2_N4") (pintype "passive"))
      (node (ref "U6") (pin "P3") (pinfunction "VCCQ3_P3") (pintype "passive"))
      (node (ref "U6") (pin "P5") (pinfunction "VCCQ5_P5") (pintype "passive"))
    )
    (net (code "4") (name "+3.3V") (class "Default")
      (node (ref "C142") (pin "2") (pinfunction "2_2") (pintype "passive"))
      (node (ref "C148") (pin "2") (pinfunction "2_2") (pintype "passive"))
      (node (ref "C151") (pin "2") (pinfunction "2_2") (pintype "passive"))
      (node (ref "C153") (pin "2") (pinfunction "2_2") (pintype "passive"))
      (node (ref "C154") (pin "2") (pinfunction "2_2") (pintype "passive"))
      (node (ref "C155") (pin "2") (pinfunction "2_2") (pintype "passive"))
      (node (ref "C156") (pin "2") (pinfunction "2_2") (pintype "passive"))
      (node (ref "C175") (pin "2") (pinfunction "2_2") (pintype "passive"))
      (node (ref "C176") (pin "2") (pinfunction "2_2") (pintype "passive"))
      (node (ref "C181") (pin "2") (pinfunction "2_2") (pintype "passive"))
      (node (ref "C182") (pin "2") (pinfunction "2_2") (pintype "passive"))
      (node (ref "C183") (pin "2") (pinfunction "2_2") (pintype "passive"))
      (node (ref "C184") (pin "2") (pinfunction "2_2") (pintype "passive"))
      (node (ref "C185") (pin "2") (pinfunction "2_2") (pintype "passive"))
      (node (ref "C186") (pin "2") (pinfunction "2_2") (pintype "passive"))
      (node (ref "L7") (pin "2") (pinfunction "2_2") (pintype "passive"))
      (node (ref "R58") (pin "2") (pinfunction "2_2") (pintype "passive"))
      (node (ref "R59") (pin "2") (pinfunction "2_2") (pintype "passive"))
      (node (ref "R73") (pin "2") (pinfunction "2_2") (pintype "passive"))
      (node (ref "R75") (pin "2") (pinfunction "2_2") (pintype "passive"))
      (node (ref "R81") (pin "2") (pinfunction "2_2") (pintype "passive"))
      (node (ref "R83") (pin "2") (pinfunction "2_2") (pintype "passive"))
      (node (ref "R87") (pin "2") (pinfunction "2_2") (pintype "passive"))
      (node (ref "R88") (pin "2") (pinfunction "2_2") (pintype "passive"))
      (node (ref "R89") (pin "2") (pinfunction "2_2") (pintype "passive"))
      (node (ref "TP4") (pin "1") (pinfunction "1_1") (pintype "passive"))
      (node (ref "U12") (pin "14") (pinfunction "VOS_14") (pintype "passive"))
      (node (ref "U13") (pin "37") (pinfunction "DVDD33_1_37") (pintype "passive"))
      (node (ref "U13") (pin "41") (pinfunction "AVDD33_2_41") (pintype "passive"))
      (node (ref "U13") (pin "44") (pinfunction "VDDREG2_44") (pintype "passive"))
      (node (ref "U13") (pin "45") (pinfunction "VDDREG1_45") (pintype "passive"))
      (node (ref "U13") (pin "6") (pinfunction "AVDD33_1_6") (pintype "passive"))
      (node (ref "U5") (pin "10") (pinfunction "VIN_10") (pintype "passive"))
      (node (ref "U5") (pin "7") (pinfunction "EN_7") (pintype "passive"))
      (node (ref "U6") (pin "E6") (pinfunction "VCC1_E6") (pintype "passive"))
      (node (ref "U6") (pin "F5") (pinfunction "VCC2_F5") (pintype "passive"))
      (node (ref "U6") (pin "J10") (pinfunction "VCC3_J10") (pintype "passive"))
      (node (ref "U6") (pin "K9") (pinfunction "VCC4_K9") (pintype "passive"))
      (node (ref "U7") (pin "8") (pinfunction "VCC_8") (pintype "passive"))
      (node (ref "U8") (pin "3") (pinfunction "EN_3") (pintype "passive"))
    )
    (net (code "5") (name "+5V") (class "Default")
      (node (ref "C169") (pin "2") (pinfunction "2_2") (pintype "passive"))
      (node (ref "C170") (pin "2") (pinfunction "2_2") (pintype "passive"))
      (node (ref "C171") (pin "2") (pinfunction "2_2") (pintype "passive"))
      (node (ref "C172") (pin "2") (pinfunction "2_2") (pintype "passive"))
      (node (ref "C177") (pin "2") (pinfunction "2_2") (pintype "passive"))
      (node (ref "C178") (pin "2") (pinfunction "2_2") (pintype "passive"))
      (node (ref "C179") (pin "2") (pinfunction "2_2") (pintype "passive"))
      (node (ref "C180") (pin "2") (pinfunction "2_2") (pintype "passive"))
      (node (ref "U10") (pin "10") (pinfunction "AVIN1_10") (pintype "passive"))
      (node (ref "U10") (pin "11") (pinfunction "AVIN2_11") (pintype "passive"))
      (node (ref "U10") (pin "12") (pinfunction "AVIN3_12") (pintype "passive"))
      (node (ref "U10") (pin "9") (pinfunction "SS/TR_9") (pintype "passive"))
      (node (ref "U11") (pin "10") (pinfunction "AVIN1_10") (pintype "passive"))
      (node (ref "U11") (pin "11") (pinfunction "AVIN2_11") (pintype "passive"))
      (node (ref "U11") (pin "12") (pinfunction "AVIN3_12") (pintype "passive"))
      (node (ref "U11") (pin "9") (pinfunction "SS/TR_9") (pintype "passive"))
      (node (ref "U12") (pin "10") (pinfunction "AVIN1_10") (pintype "passive"))
      (node (ref "U12") (pin "11") (pinfunction "AVIN2_11") (pintype "passive"))
      (node (ref "U12") (pin "12") (pinfunction "AVIN3_12") (pintype "passive"))
      (node (ref "U12") (pin "9") (pinfunction "SS/TR_9") (pintype "passive"))
      (node (ref "U9") (pin "10") (pinfunction "AVIN1_10") (pintype "passive"))
      (node (ref "U9") (pin "11") (pinfunction "AVIN2_11") (pintype "passive"))
      (node (ref "U9") (pin "12") (pinfunction "AVIN3_12") (pintype "passive"))
      (node (ref "U9") (pin "13") (pinfunction "EM_13") (pintype "passive"))
      (node (ref "U9") (pin "9") (pinfunction "SS/TR_9") (pintype "passive"))
    )
    (net (code "6") (name "/1V0_PG") (class "Default")
      (node (ref "R66") (pin "1") (pinfunction "1_1") (pintype "passive"))
      (node (ref "U10") (pin "13") (pinfunction "EM_13") (pintype "passive"))
      (node (ref "U9") (pin "4") (pinfunction "PG_4") (pintype "passive"))
    )
    (net (code "7") (name "/1V5_PG") (class "Default")
      (node (ref "R74") (pin "1") (pinfunction "1_1") (pintype "passive"))
      (node (ref "U11") (pin "4") (pinfunction "PG_4") (pintype "passive"))
      (node (ref "U12") (pin "13") (pinfunction "EM_13") (pintype "passive"))
    )
    (net (code "8") (name "/1V8_PG") (class "Default")
      (node (ref "R69") (pin "1") (pinfunction "1_1") (pintype "passive"))
      (node (ref "U10") (pin "4") (pinfunction "PG_4") (pintype "passive"))
      (node (ref "U11") (pin "13") (pinfunction "EM_13") (pintype "passive"))
    )
    (net (code "9") (name "/ADVDD10") (class "Default")
      (node (ref "C191") (pin "2") (pinfunction "2_2") (pintype "passive"))
      (node (ref "C192") (pin "2") (pinfunction "2_2") (pintype "passive"))
      (node (ref "C193") (pin "2") (pinfunction "2_2") (pintype "passive"))
      (node (ref "R78") (pin "2") (pinfunction "2_2") (pintype "passive"))
      (node (ref "U13") (pin "3") (pinfunction "ADVDD10_3_3") (pintype "passive"))
      (node (ref "U13") (pin "40") (pinfunction "ADVDD10_1_40") (pintype "passive"))
      (node (ref "U13") (pin "9") (pinfunction "ADVDD10_2_9") (pintype "passive"))
    )
    (net (code "10") (name "/DDR3_A0") (class "Default")
      (node (ref "R28") (pin "2") (pinfunction "2_2") (pintype "passive"))
      (node (ref "U3") (pin "N3") (pinfunction "A0_N3") (pintype "passive"))
      (node (ref "U4") (pin "N3") (pinfunction "A0_N3") (pintype "passive"))
    )
    (net (code "11") (name "/DDR3_A1") (class "Default")
      (node (ref "R29") (pin "2") (pinfunction "2_2") (pintype "passive"))
      (node (ref "U3") (pin "P7") (pinfunction "A1_P7") (pintype "passive"))
      (node (ref "U4") (pin "P7") (pinfunction "A1_P7") (pintype "passive"))
    )
    (net (code "12") (name "/DDR3_A2") (class "Default")
      (node (ref "R30") (pin "2") (pinfunction "2_2") (pintype "passive"))
      (node (ref "U3") (pin "P3") (pinfunction "A2_P3") (pintype "passive"))
      (node (ref "U4") (pin "P3") (pinfunction "A2_P3") (pintype "passive"))
    )
    (net (code "13") (name "/DDR3_A3") (class "Default")
      (node (ref "R31") (pin "2") (pinfunction "2_2") (pintype "passive"))
      (node (ref "U3") (pin "N2") (pinfunction "A3_N2") (pintype "passive"))
      (node (ref "U4") (pin "N2") (pinfunction "A3_N2") (pintype "passive"))
    )
    (net (code "14") (name "/DDR3_A4") (class "Default")
      (node (ref "R32") (pin "2") (pinfunction "2_2") (pintype "passive"))
      (node (ref "U3") (pin "P8") (pinfunction "A4_P8") (pintype "passive"))
      (node (ref "U4") (pin "P8") (pinfunction "A4_P8") (pintype "passive"))
    )
    (net (code "15") (name "/DDR3_A5") (class "Default")
      (node (ref "R33") (pin "2") (pinfunction "2_2") (pintype "passive"))
      (node (ref "U3") (pin "P2") (pinfunction "A5_P2") (pintype "passive"))
      (node (ref "U4") (pin "P2") (pinfunction "A5_P2") (pintype "passive"))
    )
    (net (code "16") (name "/DDR3_A6") (class "Default")
      (node (ref "R34") (pin "2") (pinfunction "2_2") (pintype "passive"))
      (node (ref "U3") (pin "R8") (pinfunction "A6_R8") (pintype "passive"))
      (node (ref "U4") (pin "R8") (pinfunction "A6_R8") (pintype "passive"))
    )
    (net (code "17") (name "/DDR3_A7") (class "Default")
      (node (ref "R35") (pin "2") (pinfunction "2_2") (pintype "passive"))
      (node (ref "U3") (pin "R2") (pinfunction "A7_R2") (pintype "passive"))
      (node (ref "U4") (pin "R2") (pinfunction "A7_R2") (pintype "passive"))
    )
    (net (code "18") (name "/DDR3_A8") (class "Default")
      (node (ref "R36") (pin "2") (pinfunction "2_2") (pintype "passive"))
      (node (ref "U3") (pin "T8") (pinfunction "A8_T8") (pintype "passive"))
      (node (ref "U4") (pin "T8") (pinfunction "A8_T8") (pintype "passive"))
    )
    (net (code "19") (name "/DDR3_A9") (class "Default")
      (node (ref "R37") (pin "2") (pinfunction "2_2") (pintype "passive"))
      (node (ref "U3") (pin "R3") (pinfunction "A9_R3") (pintype "passive"))
      (node (ref "U4") (pin "R3") (pinfunction "A9_R3") (pintype "passive"))
    )
    (net (code "20") (name "/DDR3_A10") (class "Default")
      (node (ref "R38") (pin "2") (pinfunction "2_2") (pintype "passive"))
      (node (ref "U3") (pin "L7") (pinfunction "A10/AP_L7") (pintype "passive"))
      (node (ref "U4") (pin "L7") (pinfunction "A10/AP_L7") (pintype "passive"))
    )
    (net (code "21") (name "/DDR3_A11") (class "Default")
      (node (ref "R39") (pin "2") (pinfunction "2_2") (pintype "passive"))
      (node (ref "U3") (pin "R7") (pinfunction "A11_R7") (pintype "passive"))
      (node (ref "U4") (pin "R7") (pinfunction "A11_R7") (pintype "passive"))
    )
    (net (code "22") (name "/DDR3_A12") (class "Default")
      (node (ref "R40") (pin "2") (pinfunction "2_2") (pintype "passive"))
      (node (ref "U3") (pin "N7") (pinfunction "A12/~{BC}_N7") (pintype "passive"))
      (node (ref "U4") (pin "N7") (pinfunction "A12/~{BC}_N7") (pintype "passive"))
    )
    (net (code "23") (name "/DDR3_A13") (class "Default")
      (node (ref "R41") (pin "2") (pinfunction "2_2") (pintype "passive"))
      (node (ref "U3") (pin "T3") (pinfunction "A13_T3") (pintype "passive"))
      (node (ref "U4") (pin "T3") (pinfunction "A13_T3") (pintype "passive"))
    )
    (net (code "24") (name "/DDR3_A14") (class "Default")
      (node (ref "R42") (pin "2") (pinfunction "2_2") (pintype "passive"))
      (node (ref "U3") (pin "T7") (pinfunction "A14_T7") (pintype "passive"))
      (node (ref "U4") (pin "T7") (pinfunction "A14_T7") (pintype "passive"))
    )
    (net (code "25") (name "/DDR3_BA0") (class "Default")
      (node (ref "R43") (pin "2") (pinfunction "2_2") (pintype "passive"))
      (node (ref "U3") (pin "M2") (pinfunction "BA0_M2") (pintype "passive"))
      (node (ref "U4") (pin "M2") (pinfunction "BA0_M2") (pintype "passive"))
    )
    (net (code "26") (name "/DDR3_BA1") (class "Default")
      (node (ref "R46") (pin "2") (pinfunction "2_2") (pintype "passive"))
      (node (ref "U3") (pin "N8") (pinfunction "BA1_N8") (pintype "passive"))
      (node (ref "U4") (pin "N8") (pinfunction "BA1_N8") (pintype "passive"))
    )
    (net (code "27") (name "/DDR3_BA2") (class "Default")
      (node (ref "R47") (pin "2") (pinfunction "2_2") (pintype "passive"))
      (node (ref "U3") (pin "M3") (pinfunction "BA2_M3") (pintype "passive"))
      (node (ref "U4") (pin "M3") (pinfunction "BA2_M3") (pintype "passive"))
    )
    (net (code "28") (name "/DDR3_CAS") (class "Default")
      (node (ref "R51") (pin "2") (pinfunction "2_2") (pintype "passive"))
      (node (ref "U3") (pin "K3") (pinfunction "~{CAS}_K3") (pintype "passive"))
      (node (ref "U4") (pin "K3") (pinfunction "~{CAS}_K3") (pintype "passive"))
    )
    (net (code "29") (name "/DDR3_CKE") (class "Default")
      (node (ref "R54") (pin "2") (pinfunction "2_2") (pintype "passive"))
      (node (ref "U3") (pin "K9") (pinfunction "CKE_K9") (pintype "passive"))
      (node (ref "U4") (pin "K9") (pinfunction "CKE_K9") (pintype "passive"))
    )
    (net (code "30") (name "/DDR3_CLK0_N") (class "Default")
      (node (ref "R55") (pin "1") (pinfunction "1_1") (pintype "passive"))
      (node (ref "U3") (pin "K7") (pinfunction "CLK_N_K7") (pintype "passive"))
      (node (ref "U4") (pin "K7") (pinfunction "CLK_N_K7") (pintype "passive"))
    )
    (net (code "31") (name "/DDR3_CLK0_P") (class "Default")
      (node (ref "R55") (pin "2") (pinfunction "2_2") (pintype "passive"))
      (node (ref "U3") (pin "J7") (pinfunction "CLK_P_J7") (pintype "passive"))
      (node (ref "U4") (pin "J7") (pinfunction "CLK_P_J7") (pintype "passive"))
    )
    (net (code "32") (name "/DDR3_D0") (class "Default")
      (node (ref "U3") (pin "F8") (pinfunction "DQ3_F8") (pintype "passive"))
    )
    (net (code "33") (name "/DDR3_D1") (class "Default")
      (node (ref "U3") (pin "G2") (pinfunction "DQ6_G2") (pintype "passive"))
    )
    (net (code "34") (name "/DDR3_D2") (class "Default")
      (node (ref "U3") (pin "F2") (pinfunction "DQ2_F2") (pintype "passive"))
    )
    (net (code "35") (name "/DDR3_D3") (class "Default")
      (node (ref "U3") (pin "H3") (pinfunction "DQ4_H3") (pintype "passive"))
    )
    (net (code "36") (name "/DDR3_D4") (class "Default")
      (node (ref "U3") (pin "H8") (pinfunction "DQ5_H8") (pintype "passive"))
    )
    (net (code "37") (name "/DDR3_D5") (class "Default")
      (node (ref "U3") (pin "F7") (pinfunction "DQ1_F7") (pintype "passive"))
    )
    (net (code "38") (name "/DDR3_D6") (class "Default")
      (node (ref "U3") (pin "E3") (pinfunction "DQ0_E3") (pintype "passive"))
    )
    (net (code "39") (name "/DDR3_D7") (class "Default")
      (node (ref "U3") (pin "H7") (pinfunction "DQ7_H7") (pintype "passive"))
    )
    (net (code "40") (name "/DDR3_D8") (class "Default")
      (node (ref "U3") (pin "C3") (pinfunction "DQ9_C3") (pintype "passive"))
    )
    (net (code "41") (name "/DDR3_D9") (class "Default")
      (node (ref "U3") (pin "C2") (pinfunction "DQ11_C2") (pintype "passive"))
    )
    (net (code "42") (name "/DDR3_D10") (class "Default")
      (node (ref "U3") (pin "A3") (pinfunction "DQ15_A3") (pintype "passive"))
    )
    (net (code "43") (name "/DDR3_D11") (class "Default")
      (node (ref "U3") (pin "A2") (pinfunction "DQ13_A2") (pintype "passive"))
    )
    (net (code "44") (name "/DDR3_D12") (class "Default")
      (node (ref "U3") (pin "C8") (pinfunction "DQ10_C8") (pintype "passive"))
    )
    (net (code "45") (name "/DDR3_D13") (class "Default")
      (node (ref "U3") (pin "A7") (pinfunction "DQ12_A7") (pintype "passive"))
    )
    (net (code "46") (name "/DDR3_D14") (class "Default")
      (node (ref "U3") (pin "D7") (pinfunction "DQ8_D7") (pintype "passive"))
    )
    (net (code "47") (name "/DDR3_D15") (class "Default")
      (node (ref "U3") (pin "B8") (pinfunction "DQ14_B8") (pintype "passive"))
    )
    (net (code "48") (name "/DDR3_D16") (class "Default")
      (node (ref "U4") (pin "E3") (pinfunction "DQ0_E3") (pintype "passive"))
    )
    (net (code "49") (name "/DDR3_D17") (class "Default")
      (node (ref "U4") (pin "F2") (pinfunction "DQ2_F2") (pintype "passive"))
    )
    (net (code "50") (name "/DDR3_D18") (class "Default")
      (node (ref "U4") (pin "G2") (pinfunction "DQ6_G2") (pintype "passive"))
    )
    (net (code "51") (name "/DDR3_D19") (class "Default")
      (node (ref "U4") (pin "H3") (pinfunction "DQ4_H3") (pintype "passive"))
    )
    (net (code "52") (name "/DDR3_D20") (class "Default")
      (node (ref "U4") (pin "H7") (pinfunction "DQ7_H7") (pintype "passive"))
    )
    (net (code "53") (name "/DDR3_D21") (class "Default")
      (node (ref "U4") (pin "H8") (pinfunction "DQ5_H8") (pintype "passive"))
    )
    (net (code "54") (name "/DDR3_D22") (class "Default")
      (node (ref "U4") (pin "F7") (pinfunction "DQ1_F7") (pintype "passive"))
    )
    (net (code "55") (name "/DDR3_D23") (class "Default")
      (node (ref "U4") (pin "F8") (pinfunction "DQ3_F8") (pintype "passive"))
    )
    (net (code "56") (name "/DDR3_D24") (class "Default")
      (node (ref "U4") (pin "A3") (pinfunction "DQ15_A3") (pintype "passive"))
    )
    (net (code "57") (name "/DDR3_D25") (class "Default")
      (node (ref "U4") (pin "C8") (pinfunction "DQ10_C8") (pintype "passive"))
    )
    (net (code "58") (name "/DDR3_D26") (class "Default")
      (node (ref "U4") (pin "C3") (pinfunction "DQ9_C3") (pintype "passive"))
    )
    (net (code "59") (name "/DDR3_D27") (class "Default")
      (node (ref "U4") (pin "A7") (pinfunction "DQ12_A7") (pintype "passive"))
    )
    (net (code "60") (name "/DDR3_D28") (class "Default")
      (node (ref "U4") (pin "D7") (pinfunction "DQ8_D7") (pintype "passive"))
    )
    (net (code "61") (name "/DDR3_D29") (class "Default")
      (node (ref "U4") (pin "B8") (pinfunction "DQ14_B8") (pintype "passive"))
    )
    (net (code "62") (name "/DDR3_D30") (class "Default")
      (node (ref "U4") (pin "A2") (pinfunction "DQ13_A2") (pintype "passive"))
    )
    (net (code "63") (name "/DDR3_D31") (class "Default")
      (node (ref "U4") (pin "C2") (pinfunction "DQ11_C2") (pintype "passive"))
    )
    (net (code "64") (name "/DDR3_DM0") (class "Default")
      (node (ref "U3") (pin "E7") (pinfunction "LDM_E7") (pintype "passive"))
    )
    (net (code "65") (name "/DDR3_DM1") (class "Default")
      (node (ref "U3") (pin "D3") (pinfunction "UDM_D3") (pintype "passive"))
    )
    (net (code "66") (name "/DDR3_DM2") (class "Default")
      (node (ref "U4") (pin "E7") (pinfunction "LDM_E7") (pintype "passive"))
    )
    (net (code "67") (name "/DDR3_DM3") (class "Default")
      (node (ref "U4") (pin "D3") (pinfunction "UDM_D3") (pintype "passive"))
    )
    (net (code "68") (name "/DDR3_DQS0_N") (class "Default")
      (node (ref "U3") (pin "G3") (pinfunction "~{LDQS}_G3") (pintype "passive"))
    )
    (net (code "69") (name "/DDR3_DQS0_P") (class "Default")
      (node (ref "U3") (pin "F3") (pinfunction "LDQS_F3") (pintype "passive"))
    )
    (net (code "70") (name "/DDR3_DQS1_N") (class "Default")
      (node (ref "U3") (pin "G3") (pinfunction "~{UDQS}_G3") (pintype "passive"))
    )
    (net (code "71") (name "/DDR3_DQS1_P") (class "Default")
      (node (ref "U3") (pin "C7") (pinfunction "UDQS_C7") (pintype "passive"))
    )
    (net (code "72") (name "/DDR3_DQS2_N") (class "Default")
      (node (ref "U4") (pin "G3") (pinfunction "~{LDQS}_G3") (pintype "passive"))
    )
    (net (code "73") (name "/DDR3_DQS2_P") (class "Default")
      (node (ref "U4") (pin "F3") (pinfunction "LDQS_F3") (pintype "passive"))
    )
    (net (code "74") (name "/DDR3_DQS3_N") (class "Default")
      (node (ref "U4") (pin "G3") (pinfunction "~{UDQS}_G3") (pintype "passive"))
    )
    (net (code "75") (name "/DDR3_DQS3_P") (class "Default")
      (node (ref "U4") (pin "C7") (pinfunction "UDQS_C7") (pintype "passive"))
    )
    (net (code "76") (name "/DDR3_ODT") (class "Default")
      (node (ref "R53") (pin "2") (pinfunction "2_2") (pintype "passive"))
      (node (ref "U3") (pin "K1") (pinfunction "ODT_K1") (pintype "passive"))
      (node (ref "U4") (pin "K1") (pinfunction "ODT_K1") (pintype "passive"))
    )
    (net (code "77") (name "/DDR3_RAS") (class "Default")
      (node (ref "R50") (pin "2") (pinfunction "2_2") (pintype "passive"))
      (node (ref "U3") (pin "J3") (pinfunction "~{RAS}_J3") (pintype "passive"))
      (node (ref "U4") (pin "J3") (pinfunction "~{RAS}_J3") (pintype "passive"))
    )
    (net (code "78") (name "/DDR3_RESET") (class "Default")
      (node (ref "R49") (pin "2") (pinfunction "2_2") (pintype "passive"))
      (node (ref "U3") (pin "T2") (pinfunction "~{RESET}_T2") (pintype "passive"))
      (node (ref "U4") (pin "T2") (pinfunction "~{RESET}_T2") (pintype "passive"))
    )
    (net (code "79") (name "/DDR3_S0") (class "Default")
      (node (ref "R48") (pin "2") (pinfunction "2_2") (pintype "passive"))
      (node (ref "U3") (pin "L2") (pinfunction "~{CS}_L2") (pintype "passive"))
      (node (ref "U4") (pin "L2") (pinfunction "~{CS}_L2") (pintype "passive"))
    )
    (net (code "80") (name "/DDR3_WE") (class "Default")
      (node (ref "R52") (pin "2") (pinfunction "2_2") (pintype "passive"))
      (node (ref "U3") (pin "L3") (pinfunction "~{WE}_L3") (pintype "passive"))
      (node (ref "U4") (pin "L3") (pinfunction "~{WE}_L3") (pintype "passive"))
    )
    (net (code "81") (name "/DVDD10") (class "Default")
      (node (ref "C189") (pin "2") (pinfunction "2_2") (pintype "passive"))
      (node (ref "C190") (pin "2") (pinfunction "2_2") (pintype "passive"))
      (node (ref "C194") (pin "2") (pinfunction "2_2") (pintype "passive"))
      (node (ref "C195") (pin "2") (pinfunction "2_2") (pintype "passive"))
      (node (ref "L8") (pin "2") (pinfunction "2_2") (pintype "passive"))
      (node (ref "R78") (pin "1") (pinfunction "1_1") (pintype "passive"))
      (node (ref "U13") (pin "28") (pinfunction "DVDD10_1_28") (pintype "passive"))
      (node (ref "U13") (pin "36") (pinfunction "DVDD10_2_36") (pintype "passive"))
    )
    (net (code "82") (name "/ENSWREG") (class "Default")
      (node (ref "R89") (pin "1") (pinfunction "1_1") (pintype "passive"))
      (node (ref "U13") (pin "38") (pinfunction "ENSWREG_38") (pintype "passive"))
    )
    (net (code "83") (name "/ETH_MDC") (class "Default")
      (node (ref "U13") (pin "30") (pinfunction "MDC_30") (pintype "passive"))
    )
    (net (code "84") (name "/ETH_MDIO") (class "Default")
      (node (ref "R79") (pin "2") (pinfunction "2_2") (pintype "passive"))
      (node (ref "U13") (pin "31") (pinfunction "MDIO_31") (pintype "passive"))
    )
    (net (code "85") (name "/ETH_RXCLK") (class "Default")
      (node (ref "U13") (pin "19") (pinfunction "RXCLK_19") (pintype "passive"))
    )
    (net (code "86") (name "/ETH_RXCTL") (class "Default")
      (node (ref "R91") (pin "2") (pinfunction "2_2") (pintype "passive"))
      (node (ref "U13") (pin "13") (pinfunction "RXCTL/PHY_AD2_13") (pintype "passive"))
    )
    (net (code "87") (name "/ETH_RXD0") (class "Default")
      (node (ref "R84") (pin "1") (pinfunction "1_1") (pintype "passive"))
      (node (ref "U13") (pin "14") (pinfunction "RXD0/SELRGV_14") (pintype "passive"))
    )
    (net (code "88") (name "/ETH_RXD1") (class "Default")
      (node (ref "R82") (pin "1") (pinfunction "1_1") (pintype "passive"))
      (node (ref "U13") (pin "16") (pinfunction "RXD1/TXDLY_16") (pintype "passive"))
    )
    (net (code "89") (name "/ETH_RXD2") (class "Default")
      (node (ref "R85") (pin "1") (pinfunction "1_1") (pintype "passive"))
      (node (ref "U13") (pin "17") (pinfunction "RXD2/AN0_17") (pintype "passive"))
    )
    (net (code "90") (name "/ETH_RXD3") (class "Default")
      (node (ref "R86") (pin "1") (pinfunction "1_1") (pintype "passive"))
      (node (ref "U13") (pin "18") (pinfunction "RXD3/AN1_18") (pintype "passive"))
    )
    (net (code "91") (name "/ETH_TXCK") (class "Default")
      (node (ref "U13") (pin "22") (pinfunction "TXC_22") (pintype "passive"))
    )
    (net (code "92") (name "/ETH_TXCTL") (class "Default")
      (node (ref "U13") (pin "27") (pinfunction "TXCTL_27") (pintype "passive"))
    )
    (net (code "93") (name "/ETH_TXD0") (class "Default")
      (node (ref "U13") (pin "23") (pinfunction "TXD0_23") (pintype "passive"))
    )
    (net (code "94") (name "/ETH_TXD1") (class "Default")
      (node (ref "U13") (pin "24") (pinfunction "TXD1_24") (pintype "passive"))
    )
    (net (code "95") (name "/ETH_TXD2") (class "Default")
      (node (ref "U13") (pin "25") (pinfunction "TXD2_25") (pintype "passive"))
    )
    (net (code "96") (name "/ETH_TXD3") (class "Default")
      (node (ref "U13") (pin "26") (pinfunction "TXD3_26") (pintype "passive"))
    )
    (net (code "97") (name "/INTB") (class "Default")
      (node (ref "R88") (pin "1") (pinfunction "1_1") (pintype "passive"))
      (node (ref "U13") (pin "20") (pinfunction "INTB_20") (pintype "passive"))
    )
    (net (code "98") (name "/MMC_CCLK") (class "Default")
      (node (ref "U6") (pin "M6") (pinfunction "CLK_M6") (pintype "passive"))
    )
    (net (code "99") (name "/MMC_CMD") (class "Default")
      (node (ref "R64") (pin "1") (pinfunction "1_1") (pintype "passive"))
      (node (ref "U6") (pin "M5") (pinfunction "CMD_M5") (pintype "passive"))
    )
    (net (code "100") (name "/MMC_DATA0") (class "Default")
      (node (ref "R63") (pin "1") (pinfunction "1_1") (pintype "passive"))
      (node (ref "U6") (pin "A3") (pinfunction "DAT0_A3") (pintype "passive"))
    )
    (net (code "101") (name "/MMC_DATA1") (class "Default")
      (node (ref "R62") (pin "1") (pinfunction "1_1") (pintype "passive"))
      (node (ref "U6") (pin "A4") (pinfunction "DAT1_A4") (pintype "passive"))
    )
    (net (code "102") (name "/MMC_DATA2") (class "Default")
      (node (ref "R61") (pin "1") (pinfunction "1_1") (pintype "passive"))
      (node (ref "U6") (pin "A5") (pinfunction "DAT2_A5") (pintype "passive"))
    )
    (net (code "103") (name "/MMC_DATA3") (class "Default")
      (node (ref "R60") (pin "1") (pinfunction "1_1") (pintype "passive"))
      (node (ref "U6") (pin "B2") (pinfunction "DAT3_B2") (pintype "passive"))
    )
    (net (code "104") (name "/MMC_NRST") (class "Default")
      (node (ref "C152") (pin "2") (pinfunction "2_2") (pintype "passive"))
      (node (ref "R65") (pin "1") (pinfunction "1_1") (pintype "passive"))
      (node (ref "U6") (pin "K5") (pinfunction "~{RESET}_K5") (pintype "passive"))
    )
    (net (code "105") (name "/PHY_AD0{slash}LED0") (class "Default")
      (node (ref "R83") (pin "1") (pinfunction "1_1") (pintype "passive"))
      (node (ref "U13") (pin "34") (pinfunction "LED0/PHY_AD0_34") (pintype "passive"))
    )
    (net (code "106") (name "/PHY_AD1{slash}LED1") (class "Default")
      (node (ref "R90") (pin "2") (pinfunction "2_2") (pintype "passive"))
      (node (ref "U13") (pin "35") (pinfunction "LED1/PHY_AD1_35") (pintype "passive"))
    )
    (net (code "107") (name "/PHY_MDI0_N") (class "Default")
      (node (ref "U13") (pin "2") (pinfunction "MDI[0]-_2") (pintype "passive"))
    )
    (net (code "108") (name "/PHY_MDI0_P") (class "Default")
      (node (ref "U13") (pin "1") (pinfunction "MDI[0]+_1") (pintype "passive"))
    )
    (net (code "109") (name "/PHY_MDI1_N") (class "Default")
      (node (ref "U13") (pin "5") (pinfunction "MDI[1]-_5") (pintype "passive"))
    )
    (net (code "110") (name "/PHY_MDI1_P") (class "Default")
      (node (ref "U13") (pin "4") (pinfunction "MDI[1]+_4") (pintype "passive"))
    )
    (net (code "111") (name "/PHY_MDI2_N") (class "Default")
      (node (ref "U13") (pin "8") (pinfunction "MDI[2]-_8") (pintype "passive"))
    )
    (net (code "112") (name "/PHY_MDI2_P") (class "Default")
      (node (ref "U13") (pin "7") (pinfunction "MDI[2]+_7") (pintype "passive"))
    )
    (net (code "113") (name "/PHY_MDI3_N") (class "Default")
      (node (ref "U13") (pin "11") (pinfunction "MDI[3]-_11") (pintype "passive"))
    )
    (net (code "114") (name "/PHY_MDI3_P") (class "Default")
      (node (ref "U13") (pin "10") (pinfunction "MDI[3]+_10") (pintype "passive"))
    )
    (net (code "115") (name "/PMEB") (class "Default")
      (node (ref "R87") (pin "1") (pinfunction "1_1") (pintype "passive"))
      (node (ref "U13") (pin "33") (pinfunction "PMEB_33") (pintype "passive"))
    )
    (net (code "116") (name "/PS_POR_B") (class "Default")
      (node (ref "U13") (pin "32") (pinfunction "PHYRSTB_32") (pintype "passive"))
    )
    (net (code "117") (name "/PW_GOOD") (class "Default")
      (node (ref "R75") (pin "1") (pinfunction "1_1") (pintype "passive"))
      (node (ref "U12") (pin "4") (pinfunction "PG_4") (pintype "passive"))
    )
    (net (code "118") (name "/QSPI_CS") (class "Default")
      (node (ref "R59") (pin "1") (pinfunction "1_1") (pintype "passive"))
      (node (ref "U7") (pin "1") (pinfunction "~{CS}_1") (pintype "passive"))
    )
    (net (code "119") (name "/QSPI_D0") (class "Default")
      (node (ref "U7") (pin "5") (pinfunction "DI(IO0)_5") (pintype "passive"))
    )
    (net (code "120") (name "/QSPI_D1") (class "Default")
      (node (ref "U7") (pin "2") (pinfunction "DO(IO1)_2") (pintype "passive"))
    )
    (net (code "121") (name "/QSPI_D2") (class "Default")
      (node (ref "U7") (pin "3") (pinfunction "~{WP}(IO2)_3") (pintype "passive"))
    )
    (net (code "122") (name "/QSPI_D3") (class "Default")
      (node (ref "U7") (pin "7") (pinfunction "~{HOLD}(IO3)_7") (pintype "passive"))
    )
    (net (code "123") (name "/QSPI_SCK") (class "Default")
      (node (ref "U7") (pin "6") (pinfunction "CLK_6") (pintype "passive"))
    )
    (net (code "124") (name "/REGOUT") (class "Default")
      (node (ref "L8") (pin "1") (pinfunction "1_1") (pintype "passive"))
      (node (ref "U13") (pin "48") (pinfunction "REG_OUT_48") (pintype "passive"))
    )
    (net (code "125") (name "/RSET") (class "Default")
      (node (ref "R80") (pin "2") (pinfunction "2_2") (pintype "passive"))
      (node (ref "U13") (pin "39") (pinfunction "RSET_39") (pintype "passive"))
    )
    (net (code "126") (name "/RXDLY") (class "Default")
      (node (ref "R81") (pin "1") (pinfunction "1_1") (pintype "passive"))
      (node (ref "U13") (pin "32") (pinfunction "LED2/RXDLY_32") (pintype "passive"))
    )
    (net (code "127") (name "DDRVTT") (class "Default")
      (node (ref "C144") (pin "2") (pinfunction "2_2") (pintype "passive"))
      (node (ref "C145") (pin "2") (pinfunction "2_2") (pintype "passive"))
      (node (ref "C89") (pin "2") (pinfunction "2_2") (pintype "passive"))
      (node (ref "C90") (pin "2") (pinfunction "2_2") (pintype "passive"))
      (node (ref "C91") (pin "2") (pinfunction "2_2") (pintype "passive"))
      (node (ref "C92") (pin "2") (pinfunction "2_2") (pintype "passive"))
      (node (ref "C93") (pin "2") (pinfunction "2_2") (pintype "passive"))
      (node (ref "C94") (pin "2") (pinfunction "2_2") (pintype "passive"))
      (node (ref "C95") (pin "2") (pinfunction "2_2") (pintype "passive"))
      (node (ref "C96") (pin "2") (pinfunction "2_2") (pintype "passive"))
      (node (ref "C97") (pin "2") (pinfunction "2_2") (pintype "passive"))
      (node (ref "C98") (pin "2") (pinfunction "2_2") (pintype "passive"))
      (node (ref "C99") (pin "2") (pinfunction "2_2") (pintype "passive"))
      (node (ref "R28") (pin "1") (pinfunction "1_1") (pintype "passive"))
      (node (ref "R29") (pin "1") (pinfunction "1_1") (pintype "passive"))
      (node (ref "R30") (pin "1") (pinfunction "1_1") (pintype "passive"))
      (node (ref "R31") (pin "1") (pinfunction "1_1") (pintype "passive"))
      (node (ref "R32") (pin "1") (pinfunction "1_1") (pintype "passive"))
      (node (ref "R33") (pin "1") (pinfunction "1_1") (pintype "passive"))
      (node (ref "R34") (pin "1") (pinfunction "1_1") (pintype "passive"))
      (node (ref "R35") (pin "1") (pinfunction "1_1") (pintype "passive"))
      (node (ref "R36") (pin "1") (pinfunction "1_1") (pintype "passive"))
      (node (ref "R37") (pin "1") (pinfunction "1_1") (pintype "passive"))
      (node (ref "R38") (pin "1") (pinfunction "1_1") (pintype "passive"))
      (node (ref "R39") (pin "1") (pinfunction "1_1") (pintype "passive"))
      (node (ref "R40") (pin "1") (pinfunction "1_1") (pintype "passive"))
      (node (ref "R41") (pin "1") (pinfunction "1_1") (pintype "passive"))
      (node (ref "R42") (pin "1") (pinfunction "1_1") (pintype "passive"))
      (node (ref "R43") (pin "1") (pinfunction "1_1") (pintype "passive"))
      (node (ref "R46") (pin "1") (pinfunction "1_1") (pintype "passive"))
      (node (ref "R47") (pin "1") (pinfunction "1_1") (pintype "passive"))
      (node (ref "R48") (pin "1") (pinfunction "1_1") (pintype "passive"))
      (node (ref "R50") (pin "1") (pinfunction "1_1") (pintype "passive"))
      (node (ref "R51") (pin "1") (pinfunction "1_1") (pintype "passive"))
      (node (ref "R52") (pin "1") (pinfunction "1_1") (pintype "passive"))
      (node (ref "R53") (pin "1") (pinfunction "1_1") (pintype "passive"))
      (node (ref "R54") (pin "1") (pinfunction "1_1") (pintype "passive"))
      (node (ref "U5") (pin "3") (pinfunction "VO_3") (pintype "passive"))
      (node (ref "U5") (pin "5") (pinfunction "VOSNS_5") (pintype "passive"))
    )
    (net (code "128") (name "GND") (class "Default")
      (node (ref "C102") (pin "1") (pinfunction "1_1") (pintype "passive"))
      (node (ref "C103") (pin "1") (pinfunction "1_1") (pintype "passive"))
      (node (ref "C104") (pin "1") (pinfunction "1_1") (pintype "passive"))
      (node (ref "C105") (pin "1") (pinfunction "1_1") (pintype "passive"))
      (node (ref "C106") (pin "1") (pinfunction "1_1") (pintype "passive"))
      (node (ref "C107") (pin "1") (pinfunction "1_1") (pintype "passive"))
      (node (ref "C108") (pin "1") (pinfunction "1_1") (pintype "passive"))
      (node (ref "C109") (pin "1") (pinfunction "1_1") (pintype "passive"))
      (node (ref "C110") (pin "1") (pinfunction "1_1") (pintype "passive"))
      (node (ref "C111") (pin "1") (pinfunction "1_1") (pintype "passive"))
      (node (ref "C112") (pin "1") (pinfunction "1_1") (pintype "passive"))
      (node (ref "C113") (pin "1") (pinfunction "1_1") (pintype "passive"))
      (node (ref "C114") (pin "1") (pinfunction "1_1") (pintype "passive"))
      (node (ref "C115") (pin "1") (pinfunction "1_1") (pintype "passive"))
      (node (ref "C116") (pin "1") (pinfunction "1_1") (pintype "passive"))
      (node (ref "C117") (pin "1") (pinfunction "1_1") (pintype "passive"))
      (node (ref "C118") (pin "1") (pinfunction "1_1") (pintype "passive"))
      (node (ref "C119") (pin "1") (pinfunction "1_1") (pintype "passive"))
      (node (ref "C120") (pin "1") (pinfunction "1_1") (pintype "passive"))
      (node (ref "C121") (pin "1") (pinfunction "1_1") (pintype "passive"))
      (node (ref "C122") (pin "1") (pinfunction "1_1") (pintype "passive"))
      (node (ref "C123") (pin "1") (pinfunction "1_1") (pintype "passive"))
      (node (ref "C124") (pin "1") (pinfunction "1_1") (pintype "passive"))
      (node (ref "C125") (pin "1") (pinfunction "1_1") (pintype "passive"))
      (node (ref "C126") (pin "1") (pinfunction "1_1") (pintype "passive"))
      (node (ref "C127") (pin "1") (pinfunction "1_1") (pintype "passive"))
      (node (ref "C128") (pin "1") (pinfunction "1_1") (pintype "passive"))
      (node (ref "C129") (pin "1") (pinfunction "1_1") (pintype "passive"))
      (node (ref "C130") (pin "1") (pinfunction "1_1") (pintype "passive"))
      (node (ref "C131") (pin "1") (pinfunction "1_1") (pintype "passive"))
      (node (ref "C132") (pin "1") (pinfunction "1_1") (pintype "passive"))
      (node (ref "C133") (pin "1") (pinfunction "1_1") (pintype "passive"))
      (node (ref "C134") (pin "1") (pinfunction "1_1") (pintype "passive"))
      (node (ref "C135") (pin "1") (pinfunction "1_1") (pintype "passive"))
      (node (ref "C136") (pin "1") (pinfunction "1_1") (pintype "passive"))
      (node (ref "C137") (pin "1") (pinfunction "1_1") (pintype "passive"))
      (node (ref "C138") (pin "1") (pinfunction "1_1") (pintype "passive"))
      (node (ref "C139") (pin "1") (pinfunction "1_1") (pintype "passive"))
      (node (ref "C140") (pin "1") (pinfunction "1_1") (pintype "passive"))
      (node (ref "C141") (pin "1") (pinfunction "1_1") (pintype "passive"))
      (node (ref "C142") (pin "1") (pinfunction "1_1") (pintype "passive"))
      (node (ref "C143") (pin "1") (pinfunction "1_1") (pintype "passive"))
      (node (ref "C144") (pin "1") (pinfunction "1_1") (pintype "passive"))
      (node (ref "C145") (pin "1") (pinfunction "1_1") (pintype "passive"))
      (node (ref "C146") (pin "1") (pinfunction "1_1") (pintype "passive"))
      (node (ref "C147") (pin "1") (pinfunction "1_1") (pintype "passive"))
      (node (ref "C148") (pin "1") (pinfunction "1_1") (pintype "passive"))
      (node (ref "C149") (pin "1") (pinfunction "1_1") (pintype "passive"))
      (node (ref "C150") (pin "1") (pinfunction "1_1") (pintype "passive"))
      (node (ref "C151") (pin "1") (pinfunction "1_1") (pintype "passive"))
      (node (ref "C152") (pin "1") (pinfunction "1_1") (pintype "passive"))
      (node (ref "C153") (pin "1") (pinfunction "1_1") (pintype "passive"))
      (node (ref "C154") (pin "1") (pinfunction "1_1") (pintype "passive"))
      (node (ref "C155") (pin "1") (pinfunction "1_1") (pintype "passive"))
      (node (ref "C156") (pin "1") (pinfunction "1_1") (pintype "passive"))
      (node (ref "C157") (pin "1") (pinfunction "1_1") (pintype "passive"))
      (node (ref "C158") (pin "1") (pinfunction "1_1") (pintype "passive"))
      (node (ref "C159") (pin "1") (pinfunction "1_1") (pintype "passive"))
      (node (ref "C160") (pin "1") (pinfunction "1_1") (pintype "passive"))
      (node (ref "C161") (pin "1") (pinfunction "1_1") (pintype "passive"))
      (node (ref "C162") (pin "1") (pinfunction "1_1") (pintype "passive"))
      (node (ref "C163") (pin "1") (pinfunction "1_1") (pintype "passive"))
      (node (ref "C164") (pin "1") (pinfunction "1_1") (pintype "passive"))
      (node (ref "C165") (pin "1") (pinfunction "1_1") (pintype "passive"))
      (node (ref "C166") (pin "1") (pinfunction "1_1") (pintype "passive"))
      (node (ref "C167") (pin "1") (pinfunction "1_1") (pintype "passive"))
      (node (ref "C168") (pin "1") (pinfunction "1_1") (pintype "passive"))
      (node (ref "C169") (pin "1") (pinfunction "1_1") (pintype "passive"))
      (node (ref "C170") (pin "1") (pinfunction "1_1") (pintype "passive"))
      (node (ref "C171") (pin "1") (pinfunction "1_1") (pintype "passive"))
      (node (ref "C172") (pin "1") (pinfunction "1_1") (pintype "passive"))
      (node (ref "C173") (pin "1") (pinfunction "1_1") (pintype "passive"))
      (node (ref "C174") (pin "1") (pinfunction "1_1") (pintype "passive"))
      (node (ref "C175") (pin "1") (pinfunction "1_1") (pintype "passive"))
      (node (ref "C176") (pin "1") (pinfunction "1_1") (pintype "passive"))
      (node (ref "C177") (pin "1") (pinfunction "1_1") (pintype "passive"))
      (node (ref "C178") (pin "1") (pinfunction "1_1") (pintype "passive"))
      (node (ref "C179") (pin "1") (pinfunction "1_1") (pintype "passive"))
      (node (ref "C180") (pin "1") (pinfunction "1_1") (pintype "passive"))
      (node (ref "C181") (pin "1") (pinfunction "1_1") (pintype "passive"))
      (node (ref "C182") (pin "1") (pinfunction "1_1") (pintype "passive"))
      (node (ref "C183") (pin "1") (pinfunction "1_1") (pintype "passive"))
      (node (ref "C184") (pin "1") (pinfunction "1_1") (pintype "passive"))
      (node (ref "C185") (pin "1") (pinfunction "1_1") (pintype "passive"))
      (node (ref "C186") (pin "1") (pinfunction "1_1") (pintype "passive"))
      (node (ref "C187") (pin "1") (pinfunction "1_1") (pintype "passive"))
      (node (ref "C188") (pin "1") (pinfunction "1_1") (pintype "passive"))
      (node (ref "C189") (pin "1") (pinfunction "1_1") (pintype "passive"))
      (node (ref "C190") (pin "1") (pinfunction "1_1") (pintype "passive"))
      (node (ref "C191") (pin "1") (pinfunction "1_1") (pintype "passive"))
      (node (ref "C192") (pin "1") (pinfunction "1_1") (pintype "passive"))
      (node (ref "C193") (pin "1") (pinfunction "1_1") (pintype "passive"))
      (node (ref "C194") (pin "1") (pinfunction "1_1") (pintype "passive"))
      (node (ref "C195") (pin "1") (pinfunction "1_1") (pintype "passive"))
      (node (ref "C196") (pin "2") (pinfunction "2_2") (pintype "passive"))
      (node (ref "C197") (pin "2") (pinfunction "2_2") (pintype "passive"))
      (node (ref "C198") (pin "1") (pinfunction "1_1") (pintype "passive"))
      (node (ref "C89") (pin "1") (pinfunction "1_1") (pintype "passive"))
      (node (ref "C90") (pin "1") (pinfunction "1_1") (pintype "passive"))
      (node (ref "C91") (pin "1") (pinfunction "1_1") (pintype "passive"))
      (node (ref "C92") (pin "1") (pinfunction "1_1") (pintype "passive"))
      (node (ref "C93") (pin "1") (pinfunction "1_1") (pintype "passive"))
      (node (ref "C94") (pin "1") (pinfunction "1_1") (pintype "passive"))
      (node (ref "C95") (pin "1") (pinfunction "1_1") (pintype "passive"))
      (node (ref "C96") (pin "1") (pinfunction "1_1") (pintype "passive"))
      (node (ref "C97") (pin "1") (pinfunction "1_1") (pintype "passive"))
      (node (ref "C98") (pin "1") (pinfunction "1_1") (pintype "passive"))
      (node (ref "C99") (pin "1") (pinfunction "1_1") (pintype "passive"))
      (node (ref "R44") (pin "2") (pinfunction "2_2") (pintype "passive"))
      (node (ref "R45") (pin "2") (pinfunction "2_2") (pintype "passive"))
      (node (ref "R49") (pin "1") (pinfunction "1_1") (pintype "passive"))
      (node (ref "R57") (pin "2") (pinfunction "2_2") (pintype "passive"))
      (node (ref "R70") (pin "1") (pinfunction "1_1") (pintype "passive"))
      (node (ref "R71") (pin "1") (pinfunction "1_1") (pintype "passive"))
      (node (ref "R76") (pin "1") (pinfunction "1_1") (pintype "passive"))
      (node (ref "R77") (pin "1") (pinfunction "1_1") (pintype "passive"))
      (node (ref "R80") (pin "1") (pinfunction "1_1") (pintype "passive"))
      (node (ref "R90") (pin "1") (pinfunction "1_1") (pintype "passive"))
      (node (ref "R91") (pin "1") (pinfunction "1_1") (pintype "passive"))
      (node (ref "TP5") (pin "1") (pinfunction "1_1") (pintype "passive"))
      (node (ref "U10") (pin "15") (pinfunction "PGND2_15") (pintype "passive"))
      (node (ref "U10") (pin "16") (pinfunction "PGND1_16") (pintype "passive"))
      (node (ref "U10") (pin "20") (pinfunction "TPAD_20") (pintype "passive"))
      (node (ref "U10") (pin "6") (pinfunction "AGND3_6") (pintype "passive"))
      (node (ref "U10") (pin "7") (pinfunction "FSW_7") (pintype "passive"))
      (node (ref "U10") (pin "8") (pinfunction "DEF_8") (pintype "passive"))
      (node (ref "U11") (pin "15") (pinfunction "PGND2_15") (pintype "passive"))
      (node (ref "U11") (pin "16") (pinfunction "PGND1_16") (pintype "passive"))
      (node (ref "U11") (pin "20") (pinfunction "TPAD_20") (pintype "passive"))
      (node (ref "U11") (pin "6") (pinfunction "AGND3_6") (pintype "passive"))
      (node (ref "U11") (pin "7") (pinfunction "FSW_7") (pintype "passive"))
      (node (ref "U11") (pin "8") (pinfunction "DEF_8") (pintype "passive"))
      (node (ref "U12") (pin "15") (pinfunction "PGND2_15") (pintype "passive"))
      (node (ref "U12") (pin "16") (pinfunction "PGND1_16") (pintype "passive"))
      (node (ref "U12") (pin "20") (pinfunction "TPAD_20") (pintype "passive"))
      (node (ref "U12") (pin "6") (pinfunction "AGND3_6") (pintype "passive"))
      (node (ref "U12") (pin "7") (pinfunction "FSW_7") (pintype "passive"))
      (node (ref "U12") (pin "8") (pinfunction "DEF_8") (pintype "passive"))
      (node (ref "U13") (pin "47") (pinfunction "GND_47") (pintype "passive"))
      (node (ref "U13") (pin "49") (pinfunction "EGND_49") (pintype "passive"))
      (node (ref "U3") (pin "A9") (pinfunction "VSSQ_A9") (pintype "passive"))
      (node (ref "U3") (pin "B1") (pinfunction "VSSQ_B1") (pintype "passive"))
      (node (ref "U3") (pin "B3") (pinfunction "VSSQ_B3") (pintype "passive"))
      (node (ref "U3") (pin "B9") (pinfunction "VSSQ_B9") (pintype "passive"))
      (node (ref "U3") (pin "D1") (pinfunction "VSSQ_D1") (pintype "passive"))
      (node (ref "U3") (pin "D8") (pinfunction "VSSQ_D8") (pintype "passive"))
      (node (ref "U3") (pin "E1") (pinfunction "VSSQ_E1") (pintype "passive"))
      (node (ref "U3") (pin "E2") (pinfunction "VSSQ_E2") (pintype "passive"))
      (node (ref "U3") (pin "E8") (pinfunction "VSSQ_E8") (pintype "passive"))
      (node (ref "U3") (pin "F9") (pinfunction "VSSQ_F9") (pintype "passive"))
      (node (ref "U3") (pin "G1") (pinfunction "VSSQ_G1") (pintype "passive"))
      (node (ref "U3") (pin "G8") (pinfunction "VSSQ_G8") (pintype "passive"))
      (node (ref "U3") (pin "G9") (pinfunction "VSSQ_G9") (pintype "passive"))
      (node (ref "U3") (pin "J2") (pinfunction "VSSQ_J2") (pintype "passive"))
      (node (ref "U3") (pin "J8") (pinfunction "VSSQ_J8") (pintype "passive"))
      (node (ref "U3") (pin "M1") (pinfunction "VSSQ_M1") (pintype "passive"))
      (node (ref "U3") (pin "M9") (pinfunction "VSSQ_M9") (pintype "passive"))
      (node (ref "U3") (pin "P1") (pinfunction "VSSQ_P1") (pintype "passive"))
      (node (ref "U3") (pin "P9") (pinfunction "VSSQ_P9") (pintype "passive"))
      (node (ref "U3") (pin "T1") (pinfunction "VSSQ_T1") (pintype "passive"))
      (node (ref "U3") (pin "T9") (pinfunction "VSSQ_T9") (pintype "passive"))
      (node (ref "U4") (pin "A9") (pinfunction "VSSQ_A9") (pintype "passive"))
      (node (ref "U4") (pin "B1") (pinfunction "VSSQ_B1") (pintype "passive"))
      (node (ref "U4") (pin "B3") (pinfunction "VSSQ_B3") (pintype "passive"))
      (node (ref "U4") (pin "B9") (pinfunction "VSSQ_B9") (pintype "passive"))
      (node (ref "U4") (pin "D1") (pinfunction "VSSQ_D1") (pintype "passive"))
      (node (ref "U4") (pin "D8") (pinfunction "VSSQ_D8") (pintype "passive"))
      (node (ref "U4") (pin "E1") (pinfunction "VSSQ_E1") (pintype "passive"))
      (node (ref "U4") (pin "E2") (pinfunction "VSSQ_E2") (pintype "passive"))
      (node (ref "U4") (pin "E8") (pinfunction "VSSQ_E8") (pintype "passive"))
      (node (ref "U4") (pin "F9") (pinfunction "VSSQ_F9") (pintype "passive"))
      (node (ref "U4") (pin "G1") (pinfunction "VSSQ_G1") (pintype "passive"))
      (node (ref "U4") (pin "G8") (pinfunction "VSSQ_G8") (pintype "passive"))
      (node (ref "U4") (pin "G9") (pinfunction "VSSQ_G9") (pintype "passive"))
      (node (ref "U4") (pin "J2") (pinfunction "VSSQ_J2") (pintype "passive"))
      (node (ref "U4") (pin "J8") (pinfunction "VSSQ_J8") (pintype "passive"))
      (node (ref "U4") (pin "M1") (pinfunction "VSSQ_M1") (pintype "passive"))
      (node (ref "U4") (pin "M9") (pinfunction "VSSQ_M9") (pintype "passive"))
      (node (ref "U4") (pin "P1") (pinfunction "VSSQ_P1") (pintype "passive"))
      (node (ref "U4") (pin "P9") (pinfunction "VSSQ_P9") (pintype "passive"))
      (node (ref "U4") (pin "T1") (pinfunction "VSSQ_T1") (pintype "passive"))
      (node (ref "U4") (pin "T9") (pinfunction "VSSQ_T9") (pintype "passive"))
      (node (ref "U5") (pin "11") (pinfunction "PWRGND_11") (pintype "passive"))
      (node (ref "U5") (pin "4") (pinfunction "PGND_4") (pintype "passive"))
      (node (ref "U5") (pin "8") (pinfunction "GND_8") (pintype "passive"))
      (node (ref "U6") (pin "C4") (pinfunction "VSSQ1_C4") (pintype "passive"))
      (node (ref "U6") (pin "E7") (pinfunction "VSS1_E7") (pintype "passive"))
      (node (ref "U6") (pin "G5") (pinfunction "VSS2_G5") (pintype "passive"))
      (node (ref "U6") (pin "H10") (pinfunction "VSS3_H10") (pintype "passive"))
      (node (ref "U6") (pin "K8") (pinfunction "VSS4_K8") (pintype "passive"))
      (node (ref "U6") (pin "N2") (pinfunction "VSSQ2_N2") (pintype "passive"))
      (node (ref "U6") (pin "N5") (pinfunction "VSSQ3_N5") (pintype "passive"))
      (node (ref "U6") (pin "P4") (pinfunction "VSSQ4_P4") (pintype "passive"))
      (node (ref "U6") (pin "P6") (pinfunction "VSSQ5_P6") (pintype "passive"))
      (node (ref "U7") (pin "4") (pinfunction "GND_4") (pintype "passive"))
      (node (ref "U8") (pin "2") (pinfunction "GND_2") (pintype "passive"))
      (node (ref "U9") (pin "15") (pinfunction "PGND2_15") (pintype "passive"))
      (node (ref "U9") (pin "16") (pinfunction "PGND1_16") (pintype "passive"))
      (node (ref "U9") (pin "20") (pinfunction "TPAD_20") (pintype "passive"))
      (node (ref "U9") (pin "6") (pinfunction "AGND3_6") (pintype "passive"))
      (node (ref "U9") (pin "7") (pinfunction "FSW_7") (pintype "passive"))
      (node (ref "U9") (pin "8") (pinfunction "DEF_8") (pintype "passive"))
      (node (ref "Y1") (pin "2") (pinfunction "GND_2") (pintype "passive"))
      (node (ref "Y1") (pin "4") (pinfunction "GND_4") (pintype "passive"))
    )
    (net (code "129") (name "Net-(U3-ZQ)") (class "Default")
      (node (ref "R44") (pin "1") (pinfunction "1_1") (pintype "passive"))
      (node (ref "U3") (pin "L8") (pinfunction "ZQ_L8") (pintype "passive"))
    )
    (net (code "130") (name "Net-(U4-ZQ)") (class "Default")
      (node (ref "R45") (pin "1") (pinfunction "1_1") (pintype "passive"))
      (node (ref "U4") (pin "L8") (pinfunction "ZQ_L8") (pintype "passive"))
    )
    (net (code "131") (name "Net-(U5-PGOOD)") (class "Default")
      (node (ref "R58") (pin "1") (pinfunction "1_1") (pintype "passive"))
      (node (ref "U5") (pin "9") (pinfunction "PGOOD_9") (pintype "passive"))
    )
    (net (code "132") (name "Net-(U5-REFIN)") (class "Default")
      (node (ref "C143") (pin "2") (pinfunction "2_2") (pintype "passive"))
      (node (ref "R56") (pin "2") (pinfunction "2_2") (pintype "passive"))
      (node (ref "R57") (pin "1") (pinfunction "1_1") (pintype "passive"))
      (node (ref "U5") (pin "1") (pinfunction "REFIN_1") (pintype "passive"))
    )
    (net (code "133") (name "Net-(U6B-VDDIM)") (class "Default")
      (node (ref "C161") (pin "2") (pinfunction "2_2") (pintype "passive"))
      (node (ref "U6") (pin "C2") (pinfunction "VDDIM_C2") (pintype "passive"))
    )
    (net (code "134") (name "Net-(U8-VIN)") (class "Default")
      (node (ref "C164") (pin "2") (pinfunction "2_2") (pintype "passive"))
      (node (ref "C198") (pin "2") (pinfunction "2_2") (pintype "passive"))
      (node (ref "U8") (pin "1") (pinfunction "VIN_1") (pintype "passive"))
    )
    (net (code "135") (name "Net-(U9-FB)") (class "Default")
      (node (ref "R67") (pin "1") (pinfunction "1_1") (pintype "passive"))
      (node (ref "R70") (pin "2") (pinfunction "2_2") (pintype "passive"))
      (node (ref "U9") (pin "5") (pinfunction "FB_5") (pintype "passive"))
    )
    (net (code "136") (name "Net-(U9-SW1)") (class "Default")
      (node (ref "L4") (pin "1") (pinfunction "1_1") (pintype "passive"))
      (node (ref "U9") (pin "1") (pinfunction "SW1_1") (pintype "passive"))
      (node (ref "U9") (pin "2") (pinfunction "SW2_2") (pintype "passive"))
      (node (ref "U9") (pin "3") (pinfunction "SW3_3") (pintype "passive"))
    )
    (net (code "137") (name "Net-(U10-FB)") (class "Default")
      (node (ref "R68") (pin "1") (pinfunction "1_1") (pintype "passive"))
      (node (ref "R71") (pin "2") (pinfunction "2_2") (pintype "passive"))
      (node (ref "U10") (pin "5") (pinfunction "FB_5") (pintype "passive"))
    )
    (net (code "138") (name "Net-(U10-SW1)") (class "Default")
      (node (ref "L5") (pin "1") (pinfunction "1_1") (pintype "passive"))
      (node (ref "U10") (pin "1") (pinfunction "SW1_1") (pintype "passive"))
      (node (ref "U10") (pin "2") (pinfunction "SW2_2") (pintype "passive"))
      (node (ref "U10") (pin "3") (pinfunction "SW3_3") (pintype "passive"))
    )
    (net (code "139") (name "Net-(U11-FB)") (class "Default")
      (node (ref "R72") (pin "1") (pinfunction "1_1") (pintype "passive"))
      (node (ref "R76") (pin "2") (pinfunction "2_2") (pintype "passive"))
      (node (ref "U11") (pin "5") (pinfunction "FB_5") (pintype "passive"))
    )
    (net (code "140") (name "Net-(U11-SW1)") (class "Default")
      (node (ref "L6") (pin "1") (pinfunction "1_1") (pintype "passive"))
      (node (ref "U11") (pin "1") (pinfunction "SW1_1") (pintype "passive"))
      (node (ref "U11") (pin "2") (pinfunction "SW2_2") (pintype "passive"))
      (node (ref "U11") (pin "3") (pinfunction "SW3_3") (pintype "passive"))
    )
    (net (code "141") (name "Net-(U12-FB)") (class "Default")
      (node (ref "R73") (pin "1") (pinfunction "1_1") (pintype "passive"))
      (node (ref "R77") (pin "2") (pinfunction "2_2") (pintype "passive"))
      (node (ref "U12") (pin "5") (pinfunction "FB_5") (pintype "passive"))
    )
    (net (code "142") (name "Net-(U12-SW1)") (class "Default")
      (node (ref "L7") (pin "1") (pinfunction "1_1") (pintype "passive"))
      (node (ref "U12") (pin "1") (pinfunction "SW1_1") (pintype "passive"))
      (node (ref "U12") (pin "2") (pinfunction "SW2_2") (pintype "passive"))
      (node (ref "U12") (pin "3") (pinfunction "SW3_3") (pintype "passive"))
    )
    (net (code "143") (name "Net-(U13-CKXTAL1)") (class "Default")
      (node (ref "C196") (pin "1") (pinfunction "1_1") (pintype "passive"))
      (node (ref "U13") (pin "42") (pinfunction "CKXTAL1_42") (pintype "passive"))
      (node (ref "Y1") (pin "3") (pinfunction "OUT_3") (pintype "passive"))
    )
    (net (code "144") (name "Net-(U13-CKXTAL2)") (class "Default")
      (node (ref "C197") (pin "1") (pinfunction "1_1") (pintype "passive"))
      (node (ref "U13") (pin "43") (pinfunction "CKXTAL2_43") (pintype "passive"))
      (node (ref "Y1") (pin "1") (pinfunction "IN_1") (pintype "passive"))
    )
    (net (code "145") (name "VCCIO") (class "Default")
      (node (ref "C162") (pin "2") (pinfunction "2_2") (pintype "passive"))
      (node (ref "C163") (pin "2") (pinfunction "2_2") (pintype "passive"))
      (node (ref "U8") (pin "5") (pinfunction "VOUT_5") (pintype "passive"))
    )
    (net (code "146") (name "VTTREF") (class "Default")
      (node (ref "C100") (pin "1") (pinfunction "1_1") (pintype "passive"))
      (node (ref "C101") (pin "1") (pinfunction "1_1") (pintype "passive"))
      (node (ref "C102") (pin "2") (pinfunction "2_2") (pintype "passive"))
      (node (ref "C103") (pin "2") (pinfunction "2_2") (pintype "passive"))
      (node (ref "C149") (pin "2") (pinfunction "2_2") (pintype "passive"))
      (node (ref "C150") (pin "2") (pinfunction "2_2") (pintype "passive"))
      (node (ref "U3") (pin "H1") (pinfunction "VREFDQ_H1") (pintype "passive"))
      (node (ref "U3") (pin "M8") (pinfunction "VREFCA_M8") (pintype "passive"))
      (node (ref "U4") (pin "H1") (pinfunction "VREFDQ_H1") (pintype "passive"))
      (node (ref "U4") (pin "M8") (pinfunction "VREFCA_M8") (pintype "passive"))
      (node (ref "U5") (pin "6") (pinfunction "REFOUT_6") (pintype "passive"))
    )
    (net (code "147") (name "unconnected-(U3-NC1-PadJ1)") (class "Default")
      (node (ref "U3") (pin "J1") (pinfunction "NC1_J1") (pintype "passive+no_connect"))
    )
    (net (code "148") (name "unconnected-(U3-NC2-PadJ9)") (class "Default")
      (node (ref "U3") (pin "J9") (pinfunction "NC2_J9") (pintype "passive+no_connect"))
    )
    (net (code "149") (name "unconnected-(U3-NC3-PadL1)") (class "Default")
      (node (ref "U3") (pin "L1") (pinfunction "NC3_L1") (pintype "passive+no_connect"))
    )
    (net (code "150") (name "unconnected-(U3-NC4-PadL9)") (class "Default")
      (node (ref "U3") (pin "L9") (pinfunction "NC4_L9") (pintype "passive+no_connect"))
    )
    (net (code "151") (name "unconnected-(U3-NC5-PadM7)") (class "Default")
      (node (ref "U3") (pin "M7") (pinfunction "NC5_M7") (pintype "passive+no_connect"))
    )
    (net (code "152") (name "unconnected-(U4-NC1-PadJ1)") (class "Default")
      (node (ref "U4") (pin "J1") (pinfunction "NC1_J1") (pintype "passive+no_connect"))
    )
    (net (code "153") (name "unconnected-(U4-NC2-PadJ9)") (class "Default")
      (node (ref "U4") (pin "J9") (pinfunction "NC2_J9") (pintype "passive+no_connect"))
    )
    (net (code "154") (name "unconnected-(U4-NC3-PadL1)") (class "Default")
      (node (ref "U4") (pin "L1") (pinfunction "NC3_L1") (pintype "passive+no_connect"))
    )
    (net (code "155") (name "unconnected-(U4-NC4-PadL9)") (class "Default")
      (node (ref "U4") (pin "L9") (pinfunction "NC4_L9") (pintype "passive+no_connect"))
    )
    (net (code "156") (name "unconnected-(U4-NC5-PadM7)") (class "Default")
      (node (ref "U4") (pin "M7") (pinfunction "NC5_M7") (pintype "passive+no_connect"))
    )
    (net (code "157") (name "unconnected-(U6A-DAT4-PadB3)") (class "Default")
      (node (ref "U6") (pin "B3") (pinfunction "DAT4_B3") (pintype "passive+no_connect"))
    )
    (net (code "158") (name "unconnected-(U6A-DAT5-PadB4)") (class "Default")
      (node (ref "U6") (pin "B4") (pinfunction "DAT5_B4") (pintype "passive+no_connect"))
    )
    (net (code "159") (name "unconnected-(U6A-DAT6-PadB5)") (class "Default")
      (node (ref "U6") (pin "B5") (pinfunction "DAT6_B5") (pintype "passive+no_connect"))
    )
    (net (code "160") (name "unconnected-(U6A-DAT7-PadB6)") (class "Default")
      (node (ref "U6") (pin "B6") (pinfunction "DAT7_B6") (pintype "passive+no_connect"))
    )
    (net (code "161") (name "unconnected-(U7-TP-Pad9)") (class "Default")
      (node (ref "U7") (pin "9") (pinfunction "TP_9") (pintype "passive+no_connect"))
    )
    (net (code "162") (name "unconnected-(U8-ADJ-Pad4)") (class "Default")
      (node (ref "U8") (pin "4") (pinfunction "ADJ_4") (pintype "passive+no_connect"))
    )
    (net (code "163") (name "unconnected-(U13-CLK125-Pad46)") (class "Default")
      (node (ref "U13") (pin "46") (pinfunction "CLK125_46") (pintype "passive+no_connect"))
    )
    (net (code "164") (name "unconnected-(U13-NC-Pad12)") (class "Default")
      (node (ref "U13") (pin "12") (pinfunction "NC_12") (pintype "passive+no_connect"))
    )
  )
)
